# Schematic.net
KiCad netlist of a schematic drawn in Altium Designer
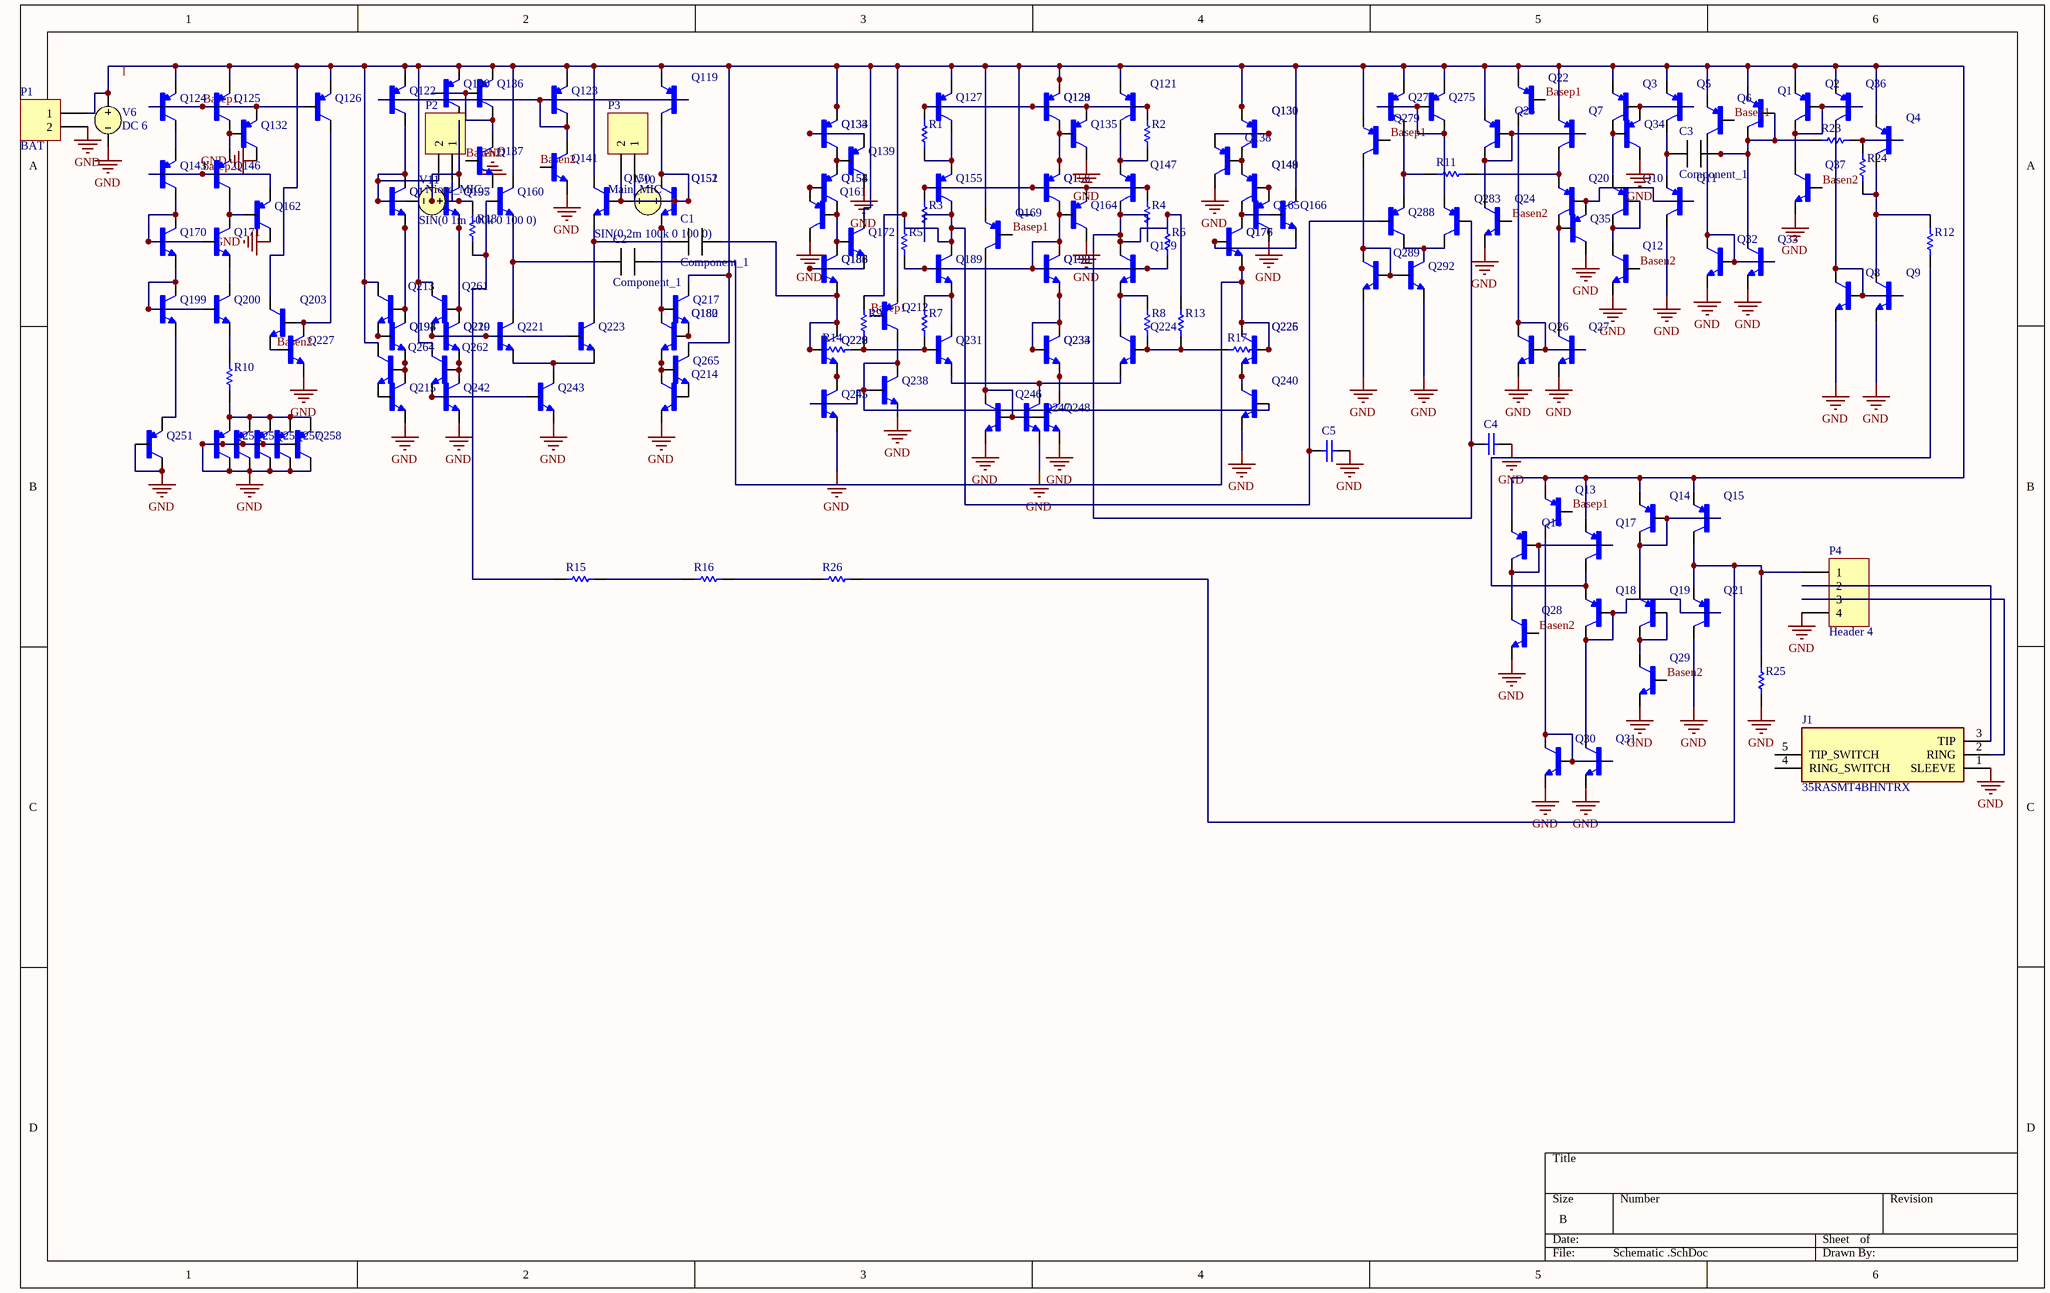
[diagram p0: Schematic .SchDoc]

(export (version "E")
  (design (tool "Eeschema 10.0.6"))
  (components
    (comp (ref "C1")
      (value "Component_1")
      (footprint "Capacitor:PCBComponent_1")
      (libsource (lib "Capacitor") (part "Component_1"))
    )
    (comp (ref "C2")
      (value "Component_1")
      (footprint "Capacitor:PCBComponent_1")
      (libsource (lib "Capacitor") (part "Component_1"))
    )
    (comp (ref "C3")
      (value "Component_1")
      (footprint "Capacitor:PCBComponent_1")
      (libsource (lib "Capacitor") (part "Component_1"))
    )
    (comp (ref "C4")
      (value "Cap")
      (footprint "RAD-0.3")
      (description "Capacitor")
      (fields (field (name "PUBLISHER") "Altium Limited"))
      (libsource (lib "Miscellaneous Devices") (part "Cap"))
    )
    (comp (ref "C5")
      (value "Cap")
      (footprint "RAD-0.3")
      (description "Capacitor")
      (fields (field (name "PUBLISHER") "Altium Limited"))
      (libsource (lib "Miscellaneous Devices") (part "Cap"))
    )
    (comp (ref "J1")
      (value "35RASMT4BHNTRX")
      (footprint "35RASMT4BHNTRX:35RASMT4BHNTRX")
      (description "Phone Connectors SMT 3.5MM PHONE JACK")
      (fields (field (name "MOUSER PART NUMBER") "502-35RASMT4BHNTRX"))
      (libsource (lib "35RASMT4BHNTRX") (part "35RASMT4BHNTRX"))
    )
    (comp (ref "P1")
      (value "BAT")
      (footprint "HDR1X2")
      (description "Header, 2-Pin")
      (fields (field (name "PUBLISHER") "Altium Limited"))
      (libsource (lib "") (part "Header 2_1"))
    )
    (comp (ref "P2")
      (value "Niose_MIC")
      (footprint "HDR1X2")
      (description "Header, 2-Pin")
      (fields (field (name "PUBLISHER") "Altium Limited"))
      (libsource (lib "Miscellaneous Connectors") (part "Header 2"))
    )
    (comp (ref "P3")
      (value "Main_MIC")
      (footprint "HDR1X2")
      (description "Header, 2-Pin")
      (fields (field (name "PUBLISHER") "Altium Limited"))
      (libsource (lib "Miscellaneous Connectors") (part "Header 2"))
    )
    (comp (ref "P4")
      (value "Header 4")
      (footprint "HDR1X4")
      (description "Header, 4-Pin")
      (fields (field (name "PUBLISHER") "Altium Limited"))
      (libsource (lib "Miscellaneous Connectors") (part "Header 4"))
    )
    (comp (ref "Q1")
      (value "KSA992FTA")
      (footprint "KSC1845_KSA992:PCBComponent_1")
      (description "TO-92, 120V, 0.05A,VA=100V,small signal PNP Bipolar Transistor")
      (fields (field (name "MP") "BC337-40 A1G") (field (name "MF") "Taiwan Semiconductor"))
      (libsource (lib "KSA992FTA") (part "KSA992FTA"))
    )
    (comp (ref "Q2")
      (value "KSA992FTA")
      (footprint "KSC1845_KSA992:PCBComponent_1")
      (description "TO-92, 120V, 0.05A,VA=100V,small signal PNP Bipolar Transistor")
      (fields (field (name "MP") "BC337-40 A1G") (field (name "MF") "Taiwan Semiconductor"))
      (libsource (lib "KSA992FTA") (part "KSA992FTA"))
    )
    (comp (ref "Q3")
      (value "KSA992FTA")
      (footprint "KSC1845_KSA992:PCBComponent_1")
      (description "TO-92, 120V, 0.05A,VA=100V,small signal PNP Bipolar Transistor")
      (fields (field (name "MP") "BC337-40 A1G") (field (name "MF") "Taiwan Semiconductor"))
      (libsource (lib "KSA992FTA") (part "KSA992FTA"))
    )
    (comp (ref "Q4")
      (value "KSA992FTA")
      (footprint "KSC1845_KSA992:PCBComponent_1")
      (description "TO-92, 120V, 0.05A,VA=100V,small signal PNP Bipolar Transistor")
      (fields (field (name "MP") "BC337-40 A1G") (field (name "MF") "Taiwan Semiconductor"))
      (libsource (lib "KSA992FTA") (part "KSA992FTA"))
    )
    (comp (ref "Q5")
      (value "KSA992FTA")
      (footprint "KSC1845_KSA992:PCBComponent_1")
      (description "TO-92, 120V, 0.05A,VA=100V,small signal PNP Bipolar Transistor")
      (fields (field (name "MP") "BC337-40 A1G") (field (name "MF") "Taiwan Semiconductor"))
      (libsource (lib "KSA992FTA") (part "KSA992FTA"))
    )
    (comp (ref "Q6")
      (value "BC560B")
      (footprint "BC560_BC550:TO92250P510H770-3")
      (description "TO-92, 45V, 0.1A, PNP Bipolar Transistor")
      (fields (field (name "MP") "BC337-40 A1G") (field (name "MF") "Taiwan Semiconductor"))
      (libsource (lib "") (part "BC560B_1"))
    )
    (comp (ref "Q7")
      (value "KSA992FTA")
      (footprint "KSC1845_KSA992:PCBComponent_1")
      (description "TO-92, 120V, 0.05A,VA=100V,small signal PNP Bipolar Transistor")
      (fields (field (name "MP") "BC337-40 A1G") (field (name "MF") "Taiwan Semiconductor"))
      (libsource (lib "KSA992FTA") (part "KSA992FTA"))
    )
    (comp (ref "Q8")
      (value "KSC1845FTA")
      (footprint "KSC1845_KSA992:PCBComponent_1")
      (description "TO-92, 120V, 0.05A,150VA,small signall NPN Bipolar Transistor")
      (fields (field (name "MP") "BC337-40 A1G") (field (name "MF") "Taiwan Semiconductor"))
      (libsource (lib "") (part "KSC1845FTA_1"))
    )
    (comp (ref "Q9")
      (value "KSC1845FTA")
      (footprint "KSC1845_KSA992:PCBComponent_1")
      (description "TO-92, 120V, 0.05A,150VA,small signall NPN Bipolar Transistor")
      (fields (field (name "MP") "BC337-40 A1G") (field (name "MF") "Taiwan Semiconductor"))
      (libsource (lib "") (part "KSC1845FTA_1"))
    )
    (comp (ref "Q10")
      (value "KSA992FTA")
      (footprint "KSC1845_KSA992:PCBComponent_1")
      (description "TO-92, 120V, 0.05A,VA=100V,small signal PNP Bipolar Transistor")
      (fields (field (name "MP") "BC337-40 A1G") (field (name "MF") "Taiwan Semiconductor"))
      (libsource (lib "KSA992FTA") (part "KSA992FTA"))
    )
    (comp (ref "Q11")
      (value "KSA992FTA")
      (footprint "KSC1845_KSA992:PCBComponent_1")
      (description "TO-92, 120V, 0.05A,VA=100V,small signal PNP Bipolar Transistor")
      (fields (field (name "MP") "BC337-40 A1G") (field (name "MF") "Taiwan Semiconductor"))
      (libsource (lib "KSA992FTA") (part "KSA992FTA"))
    )
    (comp (ref "Q12")
      (value "BC550B")
      (footprint "BC560_BC550:TO92250P510H770-3")
      (description "TO-92, 45V, 0.1A, NPN Bipolar Transistor")
      (fields (field (name "MP") "BC337-40 A1G") (field (name "MF") "Taiwan Semiconductor"))
      (libsource (lib "BC550B") (part "BC550B"))
    )
    (comp (ref "Q13")
      (value "BC560B")
      (footprint "BC560_BC550:TO92250P510H770-3")
      (description "TO-92, 45V, 0.1A, PNP Bipolar Transistor")
      (fields (field (name "MP") "BC337-40 A1G") (field (name "MF") "Taiwan Semiconductor"))
      (libsource (lib "") (part "BC560B_1"))
    )
    (comp (ref "Q14")
      (value "KSA992FTA")
      (footprint "KSC1845_KSA992:PCBComponent_1")
      (description "TO-92, 120V, 0.05A,VA=100V,small signal PNP Bipolar Transistor")
      (fields (field (name "MP") "BC337-40 A1G") (field (name "MF") "Taiwan Semiconductor"))
      (libsource (lib "KSA992FTA") (part "KSA992FTA"))
    )
    (comp (ref "Q15")
      (value "KSA992FTA")
      (footprint "KSC1845_KSA992:PCBComponent_1")
      (description "TO-92, 120V, 0.05A,VA=100V,small signal PNP Bipolar Transistor")
      (fields (field (name "MP") "BC337-40 A1G") (field (name "MF") "Taiwan Semiconductor"))
      (libsource (lib "KSA992FTA") (part "KSA992FTA"))
    )
    (comp (ref "Q16")
      (value "KSA992FTA")
      (footprint "KSC1845_KSA992:PCBComponent_1")
      (description "TO-92, 120V, 0.05A,VA=100V,small signal PNP Bipolar Transistor")
      (fields (field (name "MP") "BC337-40 A1G") (field (name "MF") "Taiwan Semiconductor"))
      (libsource (lib "KSA992FTA") (part "KSA992FTA"))
    )
    (comp (ref "Q17")
      (value "KSA992FTA")
      (footprint "KSC1845_KSA992:PCBComponent_1")
      (description "TO-92, 120V, 0.05A,VA=100V,small signal PNP Bipolar Transistor")
      (fields (field (name "MP") "BC337-40 A1G") (field (name "MF") "Taiwan Semiconductor"))
      (libsource (lib "KSA992FTA") (part "KSA992FTA"))
    )
    (comp (ref "Q18")
      (value "KSA992FTA")
      (footprint "KSC1845_KSA992:PCBComponent_1")
      (description "TO-92, 120V, 0.05A,VA=100V,small signal PNP Bipolar Transistor")
      (fields (field (name "MP") "BC337-40 A1G") (field (name "MF") "Taiwan Semiconductor"))
      (libsource (lib "KSA992FTA") (part "KSA992FTA"))
    )
    (comp (ref "Q19")
      (value "KSA992FTA")
      (footprint "KSC1845_KSA992:PCBComponent_1")
      (description "TO-92, 120V, 0.05A,VA=100V,small signal PNP Bipolar Transistor")
      (fields (field (name "MP") "BC337-40 A1G") (field (name "MF") "Taiwan Semiconductor"))
      (libsource (lib "KSA992FTA") (part "KSA992FTA"))
    )
    (comp (ref "Q20")
      (value "KSA992FTA")
      (footprint "KSC1845_KSA992:PCBComponent_1")
      (description "TO-92, 120V, 0.05A,VA=100V,small signal PNP Bipolar Transistor")
      (fields (field (name "MP") "BC337-40 A1G") (field (name "MF") "Taiwan Semiconductor"))
      (libsource (lib "KSA992FTA") (part "KSA992FTA"))
    )
    (comp (ref "Q21")
      (value "KSA992FTA")
      (footprint "KSC1845_KSA992:PCBComponent_1")
      (description "TO-92, 120V, 0.05A,VA=100V,small signal PNP Bipolar Transistor")
      (fields (field (name "MP") "BC337-40 A1G") (field (name "MF") "Taiwan Semiconductor"))
      (libsource (lib "KSA992FTA") (part "KSA992FTA"))
    )
    (comp (ref "Q22")
      (value "BC560B")
      (footprint "BC560_BC550:TO92250P510H770-3")
      (description "TO-92, 45V, 0.1A, PNP Bipolar Transistor")
      (fields (field (name "MP") "BC337-40 A1G") (field (name "MF") "Taiwan Semiconductor"))
      (libsource (lib "") (part "BC560B_1"))
    )
    (comp (ref "Q23")
      (value "KSA992FTA")
      (footprint "KSC1845_KSA992:PCBComponent_1")
      (description "TO-92, 120V, 0.05A,VA=100V,small signal PNP Bipolar Transistor")
      (fields (field (name "MP") "BC337-40 A1G") (field (name "MF") "Taiwan Semiconductor"))
      (libsource (lib "KSA992FTA") (part "KSA992FTA"))
    )
    (comp (ref "Q24")
      (value "BC550B")
      (footprint "BC560_BC550:TO92250P510H770-3")
      (description "TO-92, 45V, 0.1A, NPN Bipolar Transistor")
      (fields (field (name "MP") "BC337-40 A1G") (field (name "MF") "Taiwan Semiconductor"))
      (libsource (lib "BC550B") (part "BC550B"))
    )
    (comp (ref "Q26")
      (value "KSC1845FTA")
      (footprint "KSC1845_KSA992:PCBComponent_1")
      (description "TO-92, 120V, 0.05A,150VA,small signall NPN Bipolar Transistor")
      (fields (field (name "MP") "BC337-40 A1G") (field (name "MF") "Taiwan Semiconductor"))
      (libsource (lib "") (part "KSC1845FTA_1"))
    )
    (comp (ref "Q27")
      (value "KSC1845FTA")
      (footprint "KSC1845_KSA992:PCBComponent_1")
      (description "TO-92, 120V, 0.05A,150VA,small signall NPN Bipolar Transistor")
      (fields (field (name "MP") "BC337-40 A1G") (field (name "MF") "Taiwan Semiconductor"))
      (libsource (lib "") (part "KSC1845FTA_1"))
    )
    (comp (ref "Q28")
      (value "BC550B")
      (footprint "BC560_BC550:TO92250P510H770-3")
      (description "TO-92, 45V, 0.1A, NPN Bipolar Transistor")
      (fields (field (name "MP") "BC337-40 A1G") (field (name "MF") "Taiwan Semiconductor"))
      (libsource (lib "BC550B") (part "BC550B"))
    )
    (comp (ref "Q29")
      (value "BC550B")
      (footprint "BC560_BC550:TO92250P510H770-3")
      (description "TO-92, 45V, 0.1A, NPN Bipolar Transistor")
      (fields (field (name "MP") "BC337-40 A1G") (field (name "MF") "Taiwan Semiconductor"))
      (libsource (lib "BC550B") (part "BC550B"))
    )
    (comp (ref "Q30")
      (value "KSC1845FTA")
      (footprint "KSC1845_KSA992:PCBComponent_1")
      (description "TO-92, 120V, 0.05A,150VA,small signall NPN Bipolar Transistor")
      (fields (field (name "MP") "BC337-40 A1G") (field (name "MF") "Taiwan Semiconductor"))
      (libsource (lib "") (part "KSC1845FTA_1"))
    )
    (comp (ref "Q31")
      (value "KSC1845FTA")
      (footprint "KSC1845_KSA992:PCBComponent_1")
      (description "TO-92, 120V, 0.05A,150VA,small signall NPN Bipolar Transistor")
      (fields (field (name "MP") "BC337-40 A1G") (field (name "MF") "Taiwan Semiconductor"))
      (libsource (lib "") (part "KSC1845FTA_1"))
    )
    (comp (ref "Q32")
      (value "KSC1845FTA")
      (footprint "KSC1845_KSA992:PCBComponent_1")
      (description "TO-92, 120V, 0.05A,150VA,small signall NPN Bipolar Transistor")
      (fields (field (name "MP") "BC337-40 A1G") (field (name "MF") "Taiwan Semiconductor"))
      (libsource (lib "") (part "KSC1845FTA_1"))
    )
    (comp (ref "Q33")
      (value "KSC1845FTA")
      (footprint "KSC1845_KSA992:PCBComponent_1")
      (description "TO-92, 120V, 0.05A,150VA,small signall NPN Bipolar Transistor")
      (fields (field (name "MP") "BC337-40 A1G") (field (name "MF") "Taiwan Semiconductor"))
      (libsource (lib "") (part "KSC1845FTA_1"))
    )
    (comp (ref "Q34")
      (value "KSA992FTA")
      (footprint "KSC1845_KSA992:PCBComponent_1")
      (description "TO-92, 120V, 0.05A,VA=100V,small signal PNP Bipolar Transistor")
      (fields (field (name "MP") "BC337-40 A1G") (field (name "MF") "Taiwan Semiconductor"))
      (libsource (lib "") (part "KSA992FTA_1"))
    )
    (comp (ref "Q35")
      (value "KSA992FTA")
      (footprint "KSC1845_KSA992:PCBComponent_1")
      (description "TO-92, 120V, 0.05A,VA=100V,small signal PNP Bipolar Transistor")
      (fields (field (name "MP") "BC337-40 A1G") (field (name "MF") "Taiwan Semiconductor"))
      (libsource (lib "") (part "KSA992FTA_1"))
    )
    (comp (ref "Q36")
      (value "KSA992FTA")
      (footprint "KSC1845_KSA992:PCBComponent_1")
      (description "TO-92, 120V, 0.05A,VA=100V,small signal PNP Bipolar Transistor")
      (fields (field (name "MP") "BC337-40 A1G") (field (name "MF") "Taiwan Semiconductor"))
      (libsource (lib "KSA992FTA") (part "KSA992FTA"))
    )
    (comp (ref "Q37")
      (value "BC550B")
      (footprint "BC560_BC550:TO92250P510H770-3")
      (description "TO-92, 45V, 0.1A, NPN Bipolar Transistor")
      (fields (field (name "MP") "BC337-40 A1G") (field (name "MF") "Taiwan Semiconductor"))
      (libsource (lib "BC550B") (part "BC550B"))
    )
    (comp (ref "Q119")
      (value "KSA992FTA")
      (footprint "KSC1845_KSA992:PCBComponent_1")
      (description "TO-92, 120V, 0.05A,VA=100V,small signal PNP Bipolar Transistor")
      (fields (field (name "MP") "BC337-40 A1G") (field (name "MF") "Taiwan Semiconductor"))
      (libsource (lib "KSA992FTA") (part "KSA992FTA"))
    )
    (comp (ref "Q120")
      (value "KSA992FTA")
      (footprint "KSC1845_KSA992:PCBComponent_1")
      (description "TO-92, 120V, 0.05A,VA=100V,small signal PNP Bipolar Transistor")
      (fields (field (name "MP") "BC337-40 A1G") (field (name "MF") "Taiwan Semiconductor"))
      (libsource (lib "") (part "KSA992FTA_1"))
    )
    (comp (ref "Q121")
      (value "KSA992FTA")
      (footprint "KSC1845_KSA992:PCBComponent_1")
      (description "TO-92, 120V, 0.05A,VA=100V,small signal PNP Bipolar Transistor")
      (fields (field (name "MP") "BC337-40 A1G") (field (name "MF") "Taiwan Semiconductor"))
      (libsource (lib "KSA992FTA") (part "KSA992FTA"))
    )
    (comp (ref "Q122")
      (value "KSA992FTA")
      (footprint "KSC1845_KSA992:PCBComponent_1")
      (description "TO-92, 120V, 0.05A,VA=100V,small signal PNP Bipolar Transistor")
      (fields (field (name "MP") "BC337-40 A1G") (field (name "MF") "Taiwan Semiconductor"))
      (libsource (lib "") (part "KSA992FTA_1"))
    )
    (comp (ref "Q123")
      (value "KSA992FTA")
      (footprint "KSC1845_KSA992:PCBComponent_1")
      (description "TO-92, 120V, 0.05A,VA=100V,small signal PNP Bipolar Transistor")
      (fields (field (name "MP") "BC337-40 A1G") (field (name "MF") "Taiwan Semiconductor"))
      (libsource (lib "") (part "KSA992FTA_1"))
    )
    (comp (ref "Q124")
      (value "BC560B")
      (footprint "BC560_BC550:TO92250P510H770-3")
      (description "TO-92, 45V, 0.1A, PNP Bipolar Transistor")
      (fields (field (name "MP") "BC337-40 A1G") (field (name "MF") "Taiwan Semiconductor"))
      (libsource (lib "BC560B") (part "BC560B"))
    )
    (comp (ref "Q125")
      (value "BC560B")
      (footprint "BC560_BC550:TO92250P510H770-3")
      (description "TO-92, 45V, 0.1A, PNP Bipolar Transistor")
      (fields (field (name "MP") "BC337-40 A1G") (field (name "MF") "Taiwan Semiconductor"))
      (libsource (lib "BC560B") (part "BC560B"))
    )
    (comp (ref "Q126")
      (value "BC560B")
      (footprint "BC560_BC550:TO92250P510H770-3")
      (description "TO-92, 45V, 0.1A, PNP Bipolar Transistor")
      (fields (field (name "MP") "BC337-40 A1G") (field (name "MF") "Taiwan Semiconductor"))
      (libsource (lib "BC560B") (part "BC560B"))
    )
    (comp (ref "Q127")
      (value "KSA992FTA")
      (footprint "KSC1845_KSA992:PCBComponent_1")
      (description "TO-92, 120V, 0.05A,VA=100V,small signal PNP Bipolar Transistor")
      (fields (field (name "MP") "BC337-40 A1G") (field (name "MF") "Taiwan Semiconductor"))
      (libsource (lib "") (part "KSA992FTA_1"))
    )
    (comp (ref "Q128")
      (value "KSA992FTA")
      (footprint "KSC1845_KSA992:PCBComponent_1")
      (description "TO-92, 120V, 0.05A,VA=100V,small signal PNP Bipolar Transistor")
      (fields (field (name "MP") "BC337-40 A1G") (field (name "MF") "Taiwan Semiconductor"))
      (libsource (lib "") (part "KSA992FTA_1"))
    )
    (comp (ref "Q129")
      (value "KSA992FTA")
      (footprint "KSC1845_KSA992:PCBComponent_1")
      (description "TO-92, 120V, 0.05A,VA=100V,small signal PNP Bipolar Transistor")
      (fields (field (name "MP") "BC337-40 A1G") (field (name "MF") "Taiwan Semiconductor"))
      (libsource (lib "") (part "KSA992FTA_1"))
    )
    (comp (ref "Q130")
      (value "KSA992FTA")
      (footprint "KSC1845_KSA992:PCBComponent_1")
      (description "TO-92, 120V, 0.05A,VA=100V,small signal PNP Bipolar Transistor")
      (fields (field (name "MP") "BC337-40 A1G") (field (name "MF") "Taiwan Semiconductor"))
      (libsource (lib "KSA992FTA") (part "KSA992FTA"))
    )
    (comp (ref "Q131")
      (value "KSA992FTA")
      (footprint "KSC1845_KSA992:PCBComponent_1")
      (description "TO-92, 120V, 0.05A,VA=100V,small signal PNP Bipolar Transistor")
      (fields (field (name "MP") "BC337-40 A1G") (field (name "MF") "Taiwan Semiconductor"))
      (libsource (lib "KSA992FTA") (part "KSA992FTA"))
    )
    (comp (ref "Q132")
      (value "BC560B")
      (footprint "BC560_BC550:TO92250P510H770-3")
      (description "TO-92, 45V, 0.1A, PNP Bipolar Transistor")
      (fields (field (name "MP") "BC337-40 A1G") (field (name "MF") "Taiwan Semiconductor"))
      (libsource (lib "BC560B") (part "BC560B"))
    )
    (comp (ref "Q133")
      (value "KSA992FTA")
      (footprint "KSC1845_KSA992:PCBComponent_1")
      (description "TO-92, 120V, 0.05A,VA=100V,small signal PNP Bipolar Transistor")
      (fields (field (name "MP") "BC337-40 A1G") (field (name "MF") "Taiwan Semiconductor"))
      (libsource (lib "") (part "KSA992FTA_1"))
    )
    (comp (ref "Q134")
      (value "KSA992FTA")
      (footprint "KSC1845_KSA992:PCBComponent_1")
      (description "TO-92, 120V, 0.05A,VA=100V,small signal PNP Bipolar Transistor")
      (fields (field (name "MP") "BC337-40 A1G") (field (name "MF") "Taiwan Semiconductor"))
      (libsource (lib "") (part "KSA992FTA_1"))
    )
    (comp (ref "Q135")
      (value "KSA992FTA")
      (footprint "KSC1845_KSA992:PCBComponent_1")
      (description "TO-92, 120V, 0.05A,VA=100V,small signal PNP Bipolar Transistor")
      (fields (field (name "MP") "BC337-40 A1G") (field (name "MF") "Taiwan Semiconductor"))
      (libsource (lib "") (part "KSA992FTA_1"))
    )
    (comp (ref "Q136")
      (value "KSA992FTA")
      (footprint "KSC1845_KSA992:PCBComponent_1")
      (description "TO-92, 120V, 0.05A,VA=100V,small signal PNP Bipolar Transistor")
      (fields (field (name "MP") "BC337-40 A1G") (field (name "MF") "Taiwan Semiconductor"))
      (libsource (lib "") (part "KSA992FTA_1"))
    )
    (comp (ref "Q137")
      (value "BC550B")
      (footprint "BC560_BC550:TO92250P510H770-3")
      (description "TO-92, 45V, 0.1A, NPN Bipolar Transistor")
      (fields (field (name "MP") "BC337-40 A1G") (field (name "MF") "Taiwan Semiconductor"))
      (libsource (lib "") (part "BC550B_1"))
    )
    (comp (ref "Q138")
      (value "KSA992FTA")
      (footprint "KSC1845_KSA992:PCBComponent_1")
      (description "TO-92, 120V, 0.05A,VA=100V,small signal PNP Bipolar Transistor")
      (fields (field (name "MP") "BC337-40 A1G") (field (name "MF") "Taiwan Semiconductor"))
      (libsource (lib "KSA992FTA") (part "KSA992FTA"))
    )
    (comp (ref "Q139")
      (value "KSA992FTA")
      (footprint "KSC1845_KSA992:PCBComponent_1")
      (description "TO-92, 120V, 0.05A,VA=100V,small signal PNP Bipolar Transistor")
      (fields (field (name "MP") "BC337-40 A1G") (field (name "MF") "Taiwan Semiconductor"))
      (libsource (lib "") (part "KSA992FTA_1"))
    )
    (comp (ref "Q141")
      (value "BC550B")
      (footprint "BC560_BC550:TO92250P510H770-3")
      (description "TO-92, 45V, 0.1A, NPN Bipolar Transistor")
      (fields (field (name "MP") "BC337-40 A1G") (field (name "MF") "Taiwan Semiconductor"))
      (libsource (lib "") (part "BC550B_1"))
    )
    (comp (ref "Q143")
      (value "BC560B")
      (footprint "BC560_BC550:TO92250P510H770-3")
      (description "TO-92, 45V, 0.1A, PNP Bipolar Transistor")
      (fields (field (name "MP") "BC337-40 A1G") (field (name "MF") "Taiwan Semiconductor"))
      (libsource (lib "BC560B") (part "BC560B"))
    )
    (comp (ref "Q146")
      (value "BC560B")
      (footprint "BC560_BC550:TO92250P510H770-3")
      (description "TO-92, 45V, 0.1A, PNP Bipolar Transistor")
      (fields (field (name "MP") "BC337-40 A1G") (field (name "MF") "Taiwan Semiconductor"))
      (libsource (lib "BC560B") (part "BC560B"))
    )
    (comp (ref "Q147")
      (value "KSA992FTA")
      (footprint "KSC1845_KSA992:PCBComponent_1")
      (description "TO-92, 120V, 0.05A,VA=100V,small signal PNP Bipolar Transistor")
      (fields (field (name "MP") "BC337-40 A1G") (field (name "MF") "Taiwan Semiconductor"))
      (libsource (lib "KSA992FTA") (part "KSA992FTA"))
    )
    (comp (ref "Q148")
      (value "KSA992FTA")
      (footprint "KSC1845_KSA992:PCBComponent_1")
      (description "TO-92, 120V, 0.05A,VA=100V,small signal PNP Bipolar Transistor")
      (fields (field (name "MP") "BC337-40 A1G") (field (name "MF") "Taiwan Semiconductor"))
      (libsource (lib "KSA992FTA") (part "KSA992FTA"))
    )
    (comp (ref "Q149")
      (value "KSA992FTA")
      (footprint "KSC1845_KSA992:PCBComponent_1")
      (description "TO-92, 120V, 0.05A,VA=100V,small signal PNP Bipolar Transistor")
      (fields (field (name "MP") "BC337-40 A1G") (field (name "MF") "Taiwan Semiconductor"))
      (libsource (lib "KSA992FTA") (part "KSA992FTA"))
    )
    (comp (ref "Q150")
      (value "KSC1845FTA")
      (footprint "KSC1845_KSA992:PCBComponent_1")
      (description "TO-92, 120V, 0.05A,150VA,small signall NPN Bipolar Transistor")
      (fields (field (name "MP") "BC337-40 A1G") (field (name "MF") "Taiwan Semiconductor"))
      (libsource (lib "") (part "KSC1845FTA_1"))
    )
    (comp (ref "Q151")
      (value "KSC1845FTA")
      (footprint "KSC1845_KSA992:PCBComponent_1")
      (description "TO-92, 120V, 0.05A,150VA,small signall NPN Bipolar Transistor")
      (fields (field (name "MP") "BC337-40 A1G") (field (name "MF") "Taiwan Semiconductor"))
      (libsource (lib "") (part "KSC1845FTA_1"))
    )
    (comp (ref "Q152")
      (value "KSC1845FTA")
      (footprint "KSC1845_KSA992:PCBComponent_1")
      (description "TO-92, 120V, 0.05A,150VA,small signall NPN Bipolar Transistor")
      (fields (field (name "MP") "BC337-40 A1G") (field (name "MF") "Taiwan Semiconductor"))
      (libsource (lib "") (part "KSC1845FTA_1"))
    )
    (comp (ref "Q153")
      (value "KSA992FTA")
      (footprint "KSC1845_KSA992:PCBComponent_1")
      (description "TO-92, 120V, 0.05A,VA=100V,small signal PNP Bipolar Transistor")
      (fields (field (name "MP") "BC337-40 A1G") (field (name "MF") "Taiwan Semiconductor"))
      (libsource (lib "") (part "KSA992FTA_1"))
    )
    (comp (ref "Q154")
      (value "KSA992FTA")
      (footprint "KSC1845_KSA992:PCBComponent_1")
      (description "TO-92, 120V, 0.05A,VA=100V,small signal PNP Bipolar Transistor")
      (fields (field (name "MP") "BC337-40 A1G") (field (name "MF") "Taiwan Semiconductor"))
      (libsource (lib "") (part "KSA992FTA_1"))
    )
    (comp (ref "Q155")
      (value "KSA992FTA")
      (footprint "KSC1845_KSA992:PCBComponent_1")
      (description "TO-92, 120V, 0.05A,VA=100V,small signal PNP Bipolar Transistor")
      (fields (field (name "MP") "BC337-40 A1G") (field (name "MF") "Taiwan Semiconductor"))
      (libsource (lib "") (part "KSA992FTA_1"))
    )
    (comp (ref "Q156")
      (value "KSA992FTA")
      (footprint "KSC1845_KSA992:PCBComponent_1")
      (description "TO-92, 120V, 0.05A,VA=100V,small signal PNP Bipolar Transistor")
      (fields (field (name "MP") "BC337-40 A1G") (field (name "MF") "Taiwan Semiconductor"))
      (libsource (lib "") (part "KSA992FTA_1"))
    )
    (comp (ref "Q157")
      (value "KSA992FTA")
      (footprint "KSC1845_KSA992:PCBComponent_1")
      (description "TO-92, 120V, 0.05A,VA=100V,small signal PNP Bipolar Transistor")
      (fields (field (name "MP") "BC337-40 A1G") (field (name "MF") "Taiwan Semiconductor"))
      (libsource (lib "") (part "KSA992FTA_1"))
    )
    (comp (ref "Q158")
      (value "KSC1845FTA")
      (footprint "KSC1845_KSA992:PCBComponent_1")
      (description "TO-92, 120V, 0.05A,150VA,small signall NPN Bipolar Transistor")
      (fields (field (name "MP") "BC337-40 A1G") (field (name "MF") "Taiwan Semiconductor"))
      (libsource (lib "KSC1845FTA") (part "KSC1845FTA"))
    )
    (comp (ref "Q159")
      (value "KSC1845FTA")
      (footprint "KSC1845_KSA992:PCBComponent_1")
      (description "TO-92, 120V, 0.05A,150VA,small signall NPN Bipolar Transistor")
      (fields (field (name "MP") "BC337-40 A1G") (field (name "MF") "Taiwan Semiconductor"))
      (libsource (lib "KSC1845FTA") (part "KSC1845FTA"))
    )
    (comp (ref "Q160")
      (value "KSC1845FTA")
      (footprint "KSC1845_KSA992:PCBComponent_1")
      (description "TO-92, 120V, 0.05A,150VA,small signall NPN Bipolar Transistor")
      (fields (field (name "MP") "BC337-40 A1G") (field (name "MF") "Taiwan Semiconductor"))
      (libsource (lib "KSC1845FTA") (part "KSC1845FTA"))
    )
    (comp (ref "Q161")
      (value "KSA992FTA")
      (footprint "KSC1845_KSA992:PCBComponent_1")
      (description "TO-92, 120V, 0.05A,VA=100V,small signal PNP Bipolar Transistor")
      (fields (field (name "MP") "BC337-40 A1G") (field (name "MF") "Taiwan Semiconductor"))
      (libsource (lib "KSA992FTA") (part "KSA992FTA"))
    )
    (comp (ref "Q162")
      (value "BC560B")
      (footprint "BC560_BC550:TO92250P510H770-3")
      (description "TO-92, 45V, 0.1A, PNP Bipolar Transistor")
      (fields (field (name "MP") "BC337-40 A1G") (field (name "MF") "Taiwan Semiconductor"))
      (libsource (lib "BC560B") (part "BC560B"))
    )
    (comp (ref "Q164")
      (value "KSA992FTA")
      (footprint "KSC1845_KSA992:PCBComponent_1")
      (description "TO-92, 120V, 0.05A,VA=100V,small signal PNP Bipolar Transistor")
      (fields (field (name "MP") "BC337-40 A1G") (field (name "MF") "Taiwan Semiconductor"))
      (libsource (lib "") (part "KSA992FTA_1"))
    )
    (comp (ref "Q165")
      (value "KSA992FTA")
      (footprint "KSC1845_KSA992:PCBComponent_1")
      (description "TO-92, 120V, 0.05A,VA=100V,small signal PNP Bipolar Transistor")
      (fields (field (name "MP") "BC337-40 A1G") (field (name "MF") "Taiwan Semiconductor"))
      (libsource (lib "") (part "KSA992FTA_1"))
    )
    (comp (ref "Q166")
      (value "KSC1845FTA")
      (footprint "KSC1845_KSA992:PCBComponent_1")
      (description "TO-92, 120V, 0.05A,150VA,small signall NPN Bipolar Transistor")
      (fields (field (name "MP") "BC337-40 A1G") (field (name "MF") "Taiwan Semiconductor"))
      (libsource (lib "KSC1845FTA") (part "KSC1845FTA"))
    )
    (comp (ref "Q169")
      (value "BC560B")
      (footprint "BC560_BC550:TO92250P510H770-3")
      (description "TO-92, 45V, 0.1A, PNP Bipolar Transistor")
      (fields (field (name "MP") "BC337-40 A1G") (field (name "MF") "Taiwan Semiconductor"))
      (libsource (lib "") (part "BC560B_1"))
    )
    (comp (ref "Q170")
      (value "BC550B")
      (footprint "BC560_BC550:TO92250P510H770-3")
      (description "TO-92, 45V, 0.1A, NPN Bipolar Transistor")
      (fields (field (name "MP") "BC337-40 A1G") (field (name "MF") "Taiwan Semiconductor"))
      (libsource (lib "") (part "BC550B_1"))
    )
    (comp (ref "Q171")
      (value "BC550B")
      (footprint "BC560_BC550:TO92250P510H770-3")
      (description "TO-92, 45V, 0.1A, NPN Bipolar Transistor")
      (fields (field (name "MP") "BC337-40 A1G") (field (name "MF") "Taiwan Semiconductor"))
      (libsource (lib "") (part "BC550B_1"))
    )
    (comp (ref "Q172")
      (value "KSC1845FTA")
      (footprint "KSC1845_KSA992:PCBComponent_1")
      (description "TO-92, 120V, 0.05A,150VA,small signall NPN Bipolar Transistor")
      (fields (field (name "MP") "BC337-40 A1G") (field (name "MF") "Taiwan Semiconductor"))
      (libsource (lib "KSC1845FTA") (part "KSC1845FTA"))
    )
    (comp (ref "Q176")
      (value "KSC1845FTA")
      (footprint "KSC1845_KSA992:PCBComponent_1")
      (description "TO-92, 120V, 0.05A,150VA,small signall NPN Bipolar Transistor")
      (fields (field (name "MP") "BC337-40 A1G") (field (name "MF") "Taiwan Semiconductor"))
      (libsource (lib "KSC1845FTA") (part "KSC1845FTA"))
    )
    (comp (ref "Q177")
      (value "KSC1845FTA")
      (footprint "KSC1845_KSA992:PCBComponent_1")
      (description "TO-92, 120V, 0.05A,150VA,small signall NPN Bipolar Transistor")
      (fields (field (name "MP") "BC337-40 A1G") (field (name "MF") "Taiwan Semiconductor"))
      (libsource (lib "KSC1845FTA") (part "KSC1845FTA"))
    )
    (comp (ref "Q179")
      (value "KSC1845FTA")
      (footprint "KSC1845_KSA992:PCBComponent_1")
      (description "TO-92, 120V, 0.05A,150VA,small signall NPN Bipolar Transistor")
      (fields (field (name "MP") "BC337-40 A1G") (field (name "MF") "Taiwan Semiconductor"))
      (libsource (lib "") (part "KSC1845FTA_1"))
    )
    (comp (ref "Q180")
      (value "KSC1845FTA")
      (footprint "KSC1845_KSA992:PCBComponent_1")
      (description "TO-92, 120V, 0.05A,150VA,small signall NPN Bipolar Transistor")
      (fields (field (name "MP") "BC337-40 A1G") (field (name "MF") "Taiwan Semiconductor"))
      (libsource (lib "") (part "KSC1845FTA_1"))
    )
    (comp (ref "Q182")
      (value "KSC1845FTA")
      (footprint "KSC1845_KSA992:PCBComponent_1")
      (description "TO-92, 120V, 0.05A,150VA,small signall NPN Bipolar Transistor")
      (fields (field (name "MP") "BC337-40 A1G") (field (name "MF") "Taiwan Semiconductor"))
      (libsource (lib "") (part "KSC1845FTA_1"))
    )
    (comp (ref "Q183")
      (value "KSC1845FTA")
      (footprint "KSC1845_KSA992:PCBComponent_1")
      (description "TO-92, 120V, 0.05A,150VA,small signall NPN Bipolar Transistor")
      (fields (field (name "MP") "BC337-40 A1G") (field (name "MF") "Taiwan Semiconductor"))
      (libsource (lib "KSC1845FTA") (part "KSC1845FTA"))
    )
    (comp (ref "Q186")
      (value "KSC1845FTA")
      (footprint "KSC1845_KSA992:PCBComponent_1")
      (description "TO-92, 120V, 0.05A,150VA,small signall NPN Bipolar Transistor")
      (fields (field (name "MP") "BC337-40 A1G") (field (name "MF") "Taiwan Semiconductor"))
      (libsource (lib "KSC1845FTA") (part "KSC1845FTA"))
    )
    (comp (ref "Q189")
      (value "KSC1845FTA")
      (footprint "KSC1845_KSA992:PCBComponent_1")
      (description "TO-92, 120V, 0.05A,150VA,small signall NPN Bipolar Transistor")
      (fields (field (name "MP") "BC337-40 A1G") (field (name "MF") "Taiwan Semiconductor"))
      (libsource (lib "KSC1845FTA") (part "KSC1845FTA"))
    )
    (comp (ref "Q190")
      (value "KSC1845FTA")
      (footprint "KSC1845_KSA992:PCBComponent_1")
      (description "TO-92, 120V, 0.05A,150VA,small signall NPN Bipolar Transistor")
      (fields (field (name "MP") "BC337-40 A1G") (field (name "MF") "Taiwan Semiconductor"))
      (libsource (lib "KSC1845FTA") (part "KSC1845FTA"))
    )
    (comp (ref "Q192")
      (value "KSC1845FTA")
      (footprint "KSC1845_KSA992:PCBComponent_1")
      (description "TO-92, 120V, 0.05A,150VA,small signall NPN Bipolar Transistor")
      (fields (field (name "MP") "BC337-40 A1G") (field (name "MF") "Taiwan Semiconductor"))
      (libsource (lib "KSC1845FTA") (part "KSC1845FTA"))
    )
    (comp (ref "Q193")
      (value "KSC1845FTA")
      (footprint "KSC1845_KSA992:PCBComponent_1")
      (description "TO-92, 120V, 0.05A,150VA,small signall NPN Bipolar Transistor")
      (fields (field (name "MP") "BC337-40 A1G") (field (name "MF") "Taiwan Semiconductor"))
      (libsource (lib "KSC1845FTA") (part "KSC1845FTA"))
    )
    (comp (ref "Q194")
      (value "KSC1845FTA")
      (footprint "KSC1845_KSA992:PCBComponent_1")
      (description "TO-92, 120V, 0.05A,150VA,small signall NPN Bipolar Transistor")
      (fields (field (name "MP") "BC337-40 A1G") (field (name "MF") "Taiwan Semiconductor"))
      (libsource (lib "KSC1845FTA") (part "KSC1845FTA"))
    )
    (comp (ref "Q195")
      (value "KSC1845FTA")
      (footprint "KSC1845_KSA992:PCBComponent_1")
      (description "TO-92, 120V, 0.05A,150VA,small signall NPN Bipolar Transistor")
      (fields (field (name "MP") "BC337-40 A1G") (field (name "MF") "Taiwan Semiconductor"))
      (libsource (lib "KSC1845FTA") (part "KSC1845FTA"))
    )
    (comp (ref "Q197")
      (value "KSC1845FTA")
      (footprint "KSC1845_KSA992:PCBComponent_1")
      (description "TO-92, 120V, 0.05A,150VA,small signall NPN Bipolar Transistor")
      (fields (field (name "MP") "BC337-40 A1G") (field (name "MF") "Taiwan Semiconductor"))
      (libsource (lib "KSC1845FTA") (part "KSC1845FTA"))
    )
    (comp (ref "Q199")
      (value "BC550B")
      (footprint "BC560_BC550:TO92250P510H770-3")
      (description "TO-92, 45V, 0.1A, NPN Bipolar Transistor")
      (fields (field (name "MP") "BC337-40 A1G") (field (name "MF") "Taiwan Semiconductor"))
      (libsource (lib "") (part "BC550B_1"))
    )
    (comp (ref "Q200")
      (value "BC550B")
      (footprint "BC560_BC550:TO92250P510H770-3")
      (description "TO-92, 45V, 0.1A, NPN Bipolar Transistor")
      (fields (field (name "MP") "BC337-40 A1G") (field (name "MF") "Taiwan Semiconductor"))
      (libsource (lib "") (part "BC550B_1"))
    )
    (comp (ref "Q203")
      (value "BC550B")
      (footprint "BC560_BC550:TO92250P510H770-3")
      (description "TO-92, 45V, 0.1A, NPN Bipolar Transistor")
      (fields (field (name "MP") "BC337-40 A1G") (field (name "MF") "Taiwan Semiconductor"))
      (libsource (lib "BC550B") (part "BC550B"))
    )
    (comp (ref "Q212")
      (value "BC560B")
      (footprint "BC560_BC550:TO92250P510H770-3")
      (description "TO-92, 45V, 0.1A, PNP Bipolar Transistor")
      (fields (field (name "MP") "BC337-40 A1G") (field (name "MF") "Taiwan Semiconductor"))
      (libsource (lib "BC560B") (part "BC560B"))
    )
    (comp (ref "Q213")
      (value "KSC1845FTA")
      (footprint "KSC1845_KSA992:PCBComponent_1")
      (description "TO-92, 120V, 0.05A,150VA,small signall NPN Bipolar Transistor")
      (fields (field (name "MP") "BC337-40 A1G") (field (name "MF") "Taiwan Semiconductor"))
      (libsource (lib "") (part "KSC1845FTA_1"))
    )
    (comp (ref "Q214")
      (value "KSC1845FTA")
      (footprint "KSC1845_KSA992:PCBComponent_1")
      (description "TO-92, 120V, 0.05A,150VA,small signall NPN Bipolar Transistor")
      (fields (field (name "MP") "BC337-40 A1G") (field (name "MF") "Taiwan Semiconductor"))
      (libsource (lib "") (part "KSC1845FTA_1"))
    )
    (comp (ref "Q215")
      (value "KSC1845FTA")
      (footprint "KSC1845_KSA992:PCBComponent_1")
      (description "TO-92, 120V, 0.05A,150VA,small signall NPN Bipolar Transistor")
      (fields (field (name "MP") "BC337-40 A1G") (field (name "MF") "Taiwan Semiconductor"))
      (libsource (lib "KSC1845FTA") (part "KSC1845FTA"))
    )
    (comp (ref "Q217")
      (value "KSC1845FTA")
      (footprint "KSC1845_KSA992:PCBComponent_1")
      (description "TO-92, 120V, 0.05A,150VA,small signall NPN Bipolar Transistor")
      (fields (field (name "MP") "BC337-40 A1G") (field (name "MF") "Taiwan Semiconductor"))
      (libsource (lib "KSC1845FTA") (part "KSC1845FTA"))
    )
    (comp (ref "Q219")
      (value "KSC1845FTA")
      (footprint "KSC1845_KSA992:PCBComponent_1")
      (description "TO-92, 120V, 0.05A,150VA,small signall NPN Bipolar Transistor")
      (fields (field (name "MP") "BC337-40 A1G") (field (name "MF") "Taiwan Semiconductor"))
      (libsource (lib "KSC1845FTA") (part "KSC1845FTA"))
    )
    (comp (ref "Q220")
      (value "KSC1845FTA")
      (footprint "KSC1845_KSA992:PCBComponent_1")
      (description "TO-92, 120V, 0.05A,150VA,small signall NPN Bipolar Transistor")
      (fields (field (name "MP") "BC337-40 A1G") (field (name "MF") "Taiwan Semiconductor"))
      (libsource (lib "KSC1845FTA") (part "KSC1845FTA"))
    )
    (comp (ref "Q221")
      (value "KSC1845FTA")
      (footprint "KSC1845_KSA992:PCBComponent_1")
      (description "TO-92, 120V, 0.05A,150VA,small signall NPN Bipolar Transistor")
      (fields (field (name "MP") "BC337-40 A1G") (field (name "MF") "Taiwan Semiconductor"))
      (libsource (lib "KSC1845FTA") (part "KSC1845FTA"))
    )
    (comp (ref "Q223")
      (value "KSC1845FTA")
      (footprint "KSC1845_KSA992:PCBComponent_1")
      (description "TO-92, 120V, 0.05A,150VA,small signall NPN Bipolar Transistor")
      (fields (field (name "MP") "BC337-40 A1G") (field (name "MF") "Taiwan Semiconductor"))
      (libsource (lib "KSC1845FTA") (part "KSC1845FTA"))
    )
    (comp (ref "Q224")
      (value "KSC1845FTA")
      (footprint "KSC1845_KSA992:PCBComponent_1")
      (description "TO-92, 120V, 0.05A,150VA,small signall NPN Bipolar Transistor")
      (fields (field (name "MP") "BC337-40 A1G") (field (name "MF") "Taiwan Semiconductor"))
      (libsource (lib "") (part "KSC1845FTA_1"))
    )
    (comp (ref "Q225")
      (value "KSC1845FTA")
      (footprint "KSC1845_KSA992:PCBComponent_1")
      (description "TO-92, 120V, 0.05A,150VA,small signall NPN Bipolar Transistor")
      (fields (field (name "MP") "BC337-40 A1G") (field (name "MF") "Taiwan Semiconductor"))
      (libsource (lib "") (part "KSC1845FTA_1"))
    )
    (comp (ref "Q226")
      (value "KSC1845FTA")
      (footprint "KSC1845_KSA992:PCBComponent_1")
      (description "TO-92, 120V, 0.05A,150VA,small signall NPN Bipolar Transistor")
      (fields (field (name "MP") "BC337-40 A1G") (field (name "MF") "Taiwan Semiconductor"))
      (libsource (lib "") (part "KSC1845FTA_1"))
    )
    (comp (ref "Q227")
      (value "BC550B")
      (footprint "BC560_BC550:TO92250P510H770-3")
      (description "TO-92, 45V, 0.1A, NPN Bipolar Transistor")
      (fields (field (name "MP") "BC337-40 A1G") (field (name "MF") "Taiwan Semiconductor"))
      (libsource (lib "") (part "BC550B_1"))
    )
    (comp (ref "Q228")
      (value "KSC1845FTA")
      (footprint "KSC1845_KSA992:PCBComponent_1")
      (description "TO-92, 120V, 0.05A,150VA,small signall NPN Bipolar Transistor")
      (fields (field (name "MP") "BC337-40 A1G") (field (name "MF") "Taiwan Semiconductor"))
      (libsource (lib "KSC1845FTA") (part "KSC1845FTA"))
    )
    (comp (ref "Q229")
      (value "KSC1845FTA")
      (footprint "KSC1845_KSA992:PCBComponent_1")
      (description "TO-92, 120V, 0.05A,150VA,small signall NPN Bipolar Transistor")
      (fields (field (name "MP") "BC337-40 A1G") (field (name "MF") "Taiwan Semiconductor"))
      (libsource (lib "KSC1845FTA") (part "KSC1845FTA"))
    )
    (comp (ref "Q231")
      (value "KSC1845FTA")
      (footprint "KSC1845_KSA992:PCBComponent_1")
      (description "TO-92, 120V, 0.05A,150VA,small signall NPN Bipolar Transistor")
      (fields (field (name "MP") "BC337-40 A1G") (field (name "MF") "Taiwan Semiconductor"))
      (libsource (lib "KSC1845FTA") (part "KSC1845FTA"))
    )
    (comp (ref "Q233")
      (value "KSC1845FTA")
      (footprint "KSC1845_KSA992:PCBComponent_1")
      (description "TO-92, 120V, 0.05A,150VA,small signall NPN Bipolar Transistor")
      (fields (field (name "MP") "BC337-40 A1G") (field (name "MF") "Taiwan Semiconductor"))
      (libsource (lib "KSC1845FTA") (part "KSC1845FTA"))
    )
    (comp (ref "Q234")
      (value "KSC1845FTA")
      (footprint "KSC1845_KSA992:PCBComponent_1")
      (description "TO-92, 120V, 0.05A,150VA,small signall NPN Bipolar Transistor")
      (fields (field (name "MP") "BC337-40 A1G") (field (name "MF") "Taiwan Semiconductor"))
      (libsource (lib "KSC1845FTA") (part "KSC1845FTA"))
    )
    (comp (ref "Q238")
      (value "KSC1845FTA")
      (footprint "KSC1845_KSA992:PCBComponent_1")
      (description "TO-92, 120V, 0.05A,150VA,small signall NPN Bipolar Transistor")
      (fields (field (name "MP") "BC337-40 A1G") (field (name "MF") "Taiwan Semiconductor"))
      (libsource (lib "KSC1845FTA") (part "KSC1845FTA"))
    )
    (comp (ref "Q240")
      (value "KSC1845FTA")
      (footprint "KSC1845_KSA992:PCBComponent_1")
      (description "TO-92, 120V, 0.05A,150VA,small signall NPN Bipolar Transistor")
      (fields (field (name "MP") "BC337-40 A1G") (field (name "MF") "Taiwan Semiconductor"))
      (libsource (lib "") (part "KSC1845FTA_1"))
    )
    (comp (ref "Q242")
      (value "KSC1845FTA")
      (footprint "KSC1845_KSA992:PCBComponent_1")
      (description "TO-92, 120V, 0.05A,150VA,small signall NPN Bipolar Transistor")
      (fields (field (name "MP") "BC337-40 A1G") (field (name "MF") "Taiwan Semiconductor"))
      (libsource (lib "KSC1845FTA") (part "KSC1845FTA"))
    )
    (comp (ref "Q243")
      (value "KSC1845FTA")
      (footprint "KSC1845_KSA992:PCBComponent_1")
      (description "TO-92, 120V, 0.05A,150VA,small signall NPN Bipolar Transistor")
      (fields (field (name "MP") "BC337-40 A1G") (field (name "MF") "Taiwan Semiconductor"))
      (libsource (lib "KSC1845FTA") (part "KSC1845FTA"))
    )
    (comp (ref "Q245")
      (value "KSC1845FTA")
      (footprint "KSC1845_KSA992:PCBComponent_1")
      (description "TO-92, 120V, 0.05A,150VA,small signall NPN Bipolar Transistor")
      (fields (field (name "MP") "BC337-40 A1G") (field (name "MF") "Taiwan Semiconductor"))
      (libsource (lib "KSC1845FTA") (part "KSC1845FTA"))
    )
    (comp (ref "Q246")
      (value "KSC1845FTA")
      (footprint "KSC1845_KSA992:PCBComponent_1")
      (description "TO-92, 120V, 0.05A,150VA,small signall NPN Bipolar Transistor")
      (fields (field (name "MP") "BC337-40 A1G") (field (name "MF") "Taiwan Semiconductor"))
      (libsource (lib "") (part "KSC1845FTA_1"))
    )
    (comp (ref "Q247")
      (value "KSC1845FTA")
      (footprint "KSC1845_KSA992:PCBComponent_1")
      (description "TO-92, 120V, 0.05A,150VA,small signall NPN Bipolar Transistor")
      (fields (field (name "MP") "BC337-40 A1G") (field (name "MF") "Taiwan Semiconductor"))
      (libsource (lib "KSC1845FTA") (part "KSC1845FTA"))
    )
    (comp (ref "Q248")
      (value "KSC1845FTA")
      (footprint "KSC1845_KSA992:PCBComponent_1")
      (description "TO-92, 120V, 0.05A,150VA,small signall NPN Bipolar Transistor")
      (fields (field (name "MP") "BC337-40 A1G") (field (name "MF") "Taiwan Semiconductor"))
      (libsource (lib "KSC1845FTA") (part "KSC1845FTA"))
    )
    (comp (ref "Q251")
      (value "BC560B")
      (footprint "BC560_BC550:TO92250P510H770-3")
      (description "TO-92, 45V, 0.1A, PNP Bipolar Transistor")
      (fields (field (name "MP") "BC337-40 A1G") (field (name "MF") "Taiwan Semiconductor"))
      (libsource (lib "BC560B") (part "BC560B"))
    )
    (comp (ref "Q252")
      (value "BC560B")
      (footprint "BC560_BC550:TO92250P510H770-3")
      (description "TO-92, 45V, 0.1A, PNP Bipolar Transistor")
      (fields (field (name "MP") "BC337-40 A1G") (field (name "MF") "Taiwan Semiconductor"))
      (libsource (lib "BC560B") (part "BC560B"))
    )
    (comp (ref "Q254")
      (value "BC560B")
      (footprint "BC560_BC550:TO92250P510H770-3")
      (description "TO-92, 45V, 0.1A, PNP Bipolar Transistor")
      (fields (field (name "MP") "BC337-40 A1G") (field (name "MF") "Taiwan Semiconductor"))
      (libsource (lib "BC560B") (part "BC560B"))
    )
    (comp (ref "Q255")
      (value "BC560B")
      (footprint "BC560_BC550:TO92250P510H770-3")
      (description "TO-92, 45V, 0.1A, PNP Bipolar Transistor")
      (fields (field (name "MP") "BC337-40 A1G") (field (name "MF") "Taiwan Semiconductor"))
      (libsource (lib "BC560B") (part "BC560B"))
    )
    (comp (ref "Q257")
      (value "BC560B")
      (footprint "BC560_BC550:TO92250P510H770-3")
      (description "TO-92, 45V, 0.1A, PNP Bipolar Transistor")
      (fields (field (name "MP") "BC337-40 A1G") (field (name "MF") "Taiwan Semiconductor"))
      (libsource (lib "BC560B") (part "BC560B"))
    )
    (comp (ref "Q258")
      (value "BC560B")
      (footprint "BC560_BC550:TO92250P510H770-3")
      (description "TO-92, 45V, 0.1A, PNP Bipolar Transistor")
      (fields (field (name "MP") "BC337-40 A1G") (field (name "MF") "Taiwan Semiconductor"))
      (libsource (lib "BC560B") (part "BC560B"))
    )
    (comp (ref "Q261")
      (value "KSC1845FTA")
      (footprint "KSC1845_KSA992:PCBComponent_1")
      (description "TO-92, 120V, 0.05A,150VA,small signall NPN Bipolar Transistor")
      (fields (field (name "MP") "BC337-40 A1G") (field (name "MF") "Taiwan Semiconductor"))
      (libsource (lib "") (part "KSC1845FTA_1"))
    )
    (comp (ref "Q262")
      (value "KSC1845FTA")
      (footprint "KSC1845_KSA992:PCBComponent_1")
      (description "TO-92, 120V, 0.05A,150VA,small signall NPN Bipolar Transistor")
      (fields (field (name "MP") "BC337-40 A1G") (field (name "MF") "Taiwan Semiconductor"))
      (libsource (lib "") (part "KSC1845FTA_1"))
    )
    (comp (ref "Q264")
      (value "KSC1845FTA")
      (footprint "KSC1845_KSA992:PCBComponent_1")
      (description "TO-92, 120V, 0.05A,150VA,small signall NPN Bipolar Transistor")
      (fields (field (name "MP") "BC337-40 A1G") (field (name "MF") "Taiwan Semiconductor"))
      (libsource (lib "") (part "KSC1845FTA_1"))
    )
    (comp (ref "Q265")
      (value "KSC1845FTA")
      (footprint "KSC1845_KSA992:PCBComponent_1")
      (description "TO-92, 120V, 0.05A,150VA,small signall NPN Bipolar Transistor")
      (fields (field (name "MP") "BC337-40 A1G") (field (name "MF") "Taiwan Semiconductor"))
      (libsource (lib "KSC1845FTA") (part "KSC1845FTA"))
    )
    (comp (ref "Q274")
      (value "KSA992FTA")
      (footprint "KSC1845_KSA992:PCBComponent_1")
      (description "TO-92, 120V, 0.05A,VA=100V,small signal PNP Bipolar Transistor")
      (fields (field (name "MP") "BC337-40 A1G") (field (name "MF") "Taiwan Semiconductor"))
      (libsource (lib "") (part "KSA992FTA_1"))
    )
    (comp (ref "Q275")
      (value "KSA992FTA")
      (footprint "KSC1845_KSA992:PCBComponent_1")
      (description "TO-92, 120V, 0.05A,VA=100V,small signal PNP Bipolar Transistor")
      (fields (field (name "MP") "BC337-40 A1G") (field (name "MF") "Taiwan Semiconductor"))
      (libsource (lib "") (part "KSA992FTA_1"))
    )
    (comp (ref "Q279")
      (value "BC560B")
      (footprint "BC560_BC550:TO92250P510H770-3")
      (description "TO-92, 45V, 0.1A, PNP Bipolar Transistor")
      (fields (field (name "MP") "BC337-40 A1G") (field (name "MF") "Taiwan Semiconductor"))
      (libsource (lib "") (part "BC560B_1"))
    )
    (comp (ref "Q283")
      (value "KSA992FTA")
      (footprint "KSC1845_KSA992:PCBComponent_1")
      (description "TO-92, 120V, 0.05A,VA=100V,small signal PNP Bipolar Transistor")
      (fields (field (name "MP") "BC337-40 A1G") (field (name "MF") "Taiwan Semiconductor"))
      (libsource (lib "KSA992FTA") (part "KSA992FTA"))
    )
    (comp (ref "Q288")
      (value "KSA992FTA")
      (footprint "KSC1845_KSA992:PCBComponent_1")
      (description "TO-92, 120V, 0.05A,VA=100V,small signal PNP Bipolar Transistor")
      (fields (field (name "MP") "BC337-40 A1G") (field (name "MF") "Taiwan Semiconductor"))
      (libsource (lib "") (part "KSA992FTA_1"))
    )
    (comp (ref "Q289")
      (value "KSC1845FTA")
      (footprint "KSC1845_KSA992:PCBComponent_1")
      (description "TO-92, 120V, 0.05A,150VA,small signall NPN Bipolar Transistor")
      (fields (field (name "MP") "BC337-40 A1G") (field (name "MF") "Taiwan Semiconductor"))
      (libsource (lib "") (part "KSC1845FTA_1"))
    )
    (comp (ref "Q292")
      (value "KSC1845FTA")
      (footprint "KSC1845_KSA992:PCBComponent_1")
      (description "TO-92, 120V, 0.05A,150VA,small signall NPN Bipolar Transistor")
      (fields (field (name "MP") "BC337-40 A1G") (field (name "MF") "Taiwan Semiconductor"))
      (libsource (lib "KSC1845FTA") (part "KSC1845FTA"))
    )
    (comp (ref "R1")
      (value "Res1")
      (footprint "AXIAL-0.3")
      (description "Resistor")
      (fields (field (name "PUBLISHER") "Altium Limited"))
      (libsource (lib "Miscellaneous Devices") (part "Res1"))
    )
    (comp (ref "R2")
      (value "Res1")
      (footprint "AXIAL-0.3")
      (description "Resistor")
      (fields (field (name "PUBLISHER") "Altium Limited"))
      (libsource (lib "Miscellaneous Devices") (part "Res1"))
    )
    (comp (ref "R3")
      (value "Res1")
      (footprint "AXIAL-0.3")
      (description "Resistor")
      (fields (field (name "PUBLISHER") "Altium Limited"))
      (libsource (lib "Miscellaneous Devices") (part "Res1"))
    )
    (comp (ref "R4")
      (value "Res1")
      (footprint "AXIAL-0.3")
      (description "Resistor")
      (fields (field (name "PUBLISHER") "Altium Limited"))
      (libsource (lib "Miscellaneous Devices") (part "Res1"))
    )
    (comp (ref "R5")
      (value "Res1")
      (footprint "AXIAL-0.3")
      (description "Resistor")
      (fields (field (name "PUBLISHER") "Altium Limited"))
      (libsource (lib "Miscellaneous Devices") (part "Res1"))
    )
    (comp (ref "R6")
      (value "Res1")
      (footprint "AXIAL-0.3")
      (description "Resistor")
      (fields (field (name "PUBLISHER") "Altium Limited"))
      (libsource (lib "Miscellaneous Devices") (part "Res1"))
    )
    (comp (ref "R7")
      (value "Res1")
      (footprint "AXIAL-0.3")
      (description "Resistor")
      (fields (field (name "PUBLISHER") "Altium Limited"))
      (libsource (lib "Miscellaneous Devices") (part "Res1"))
    )
    (comp (ref "R8")
      (value "Res1")
      (footprint "AXIAL-0.3")
      (description "Resistor")
      (fields (field (name "PUBLISHER") "Altium Limited"))
      (libsource (lib "Miscellaneous Devices") (part "Res1"))
    )
    (comp (ref "R9")
      (value "Res1")
      (footprint "AXIAL-0.3")
      (description "Resistor")
      (fields (field (name "PUBLISHER") "Altium Limited"))
      (libsource (lib "Miscellaneous Devices") (part "Res1"))
    )
    (comp (ref "R10")
      (value "Res1")
      (footprint "AXIAL-0.3")
      (description "Resistor")
      (fields (field (name "PUBLISHER") "Altium Limited"))
      (libsource (lib "Miscellaneous Devices") (part "Res1"))
    )
    (comp (ref "R11")
      (value "Res1")
      (footprint "AXIAL-0.3")
      (description "Resistor")
      (fields (field (name "PUBLISHER") "Altium Limited"))
      (libsource (lib "Miscellaneous Devices") (part "Res1"))
    )
    (comp (ref "R12")
      (value "Res1")
      (footprint "AXIAL-0.3")
      (description "Resistor")
      (fields (field (name "PUBLISHER") "Altium Limited"))
      (libsource (lib "Miscellaneous Devices") (part "Res1"))
    )
    (comp (ref "R13")
      (value "Res1")
      (footprint "AXIAL-0.3")
      (description "Resistor")
      (fields (field (name "PUBLISHER") "Altium Limited"))
      (libsource (lib "Miscellaneous Devices") (part "Res1"))
    )
    (comp (ref "R14")
      (value "Res1")
      (footprint "AXIAL-0.3")
      (description "Resistor")
      (fields (field (name "PUBLISHER") "Altium Limited"))
      (libsource (lib "Miscellaneous Devices") (part "Res1"))
    )
    (comp (ref "R15")
      (value "Res1")
      (footprint "PCBComponent_1")
      (description "Resistor")
      (fields (field (name "PUBLISHER") "Altium Limited"))
      (libsource (lib "Miscellaneous Devices") (part "Res1"))
    )
    (comp (ref "R16")
      (value "Res1")
      (footprint "PCBComponent_1")
      (description "Resistor")
      (fields (field (name "PUBLISHER") "Altium Limited"))
      (libsource (lib "Miscellaneous Devices") (part "Res1"))
    )
    (comp (ref "R17")
      (value "Res1")
      (footprint "AXIAL-0.3")
      (description "Resistor")
      (fields (field (name "PUBLISHER") "Altium Limited"))
      (libsource (lib "Miscellaneous Devices") (part "Res1"))
    )
    (comp (ref "R18")
      (value "Res1")
      (footprint "AXIAL-0.3")
      (description "Resistor")
      (fields (field (name "PUBLISHER") "Altium Limited"))
      (libsource (lib "Miscellaneous Devices") (part "Res1"))
    )
    (comp (ref "R23")
      (value "Res1")
      (footprint "AXIAL-0.3")
      (description "Resistor")
      (fields (field (name "PUBLISHER") "Altium Limited"))
      (libsource (lib "Miscellaneous Devices") (part "Res1"))
    )
    (comp (ref "R24")
      (value "Res1")
      (footprint "AXIAL-0.3")
      (description "Resistor")
      (fields (field (name "PUBLISHER") "Altium Limited"))
      (libsource (lib "Miscellaneous Devices") (part "Res1"))
    )
    (comp (ref "R25")
      (value "Res1")
      (footprint "AXIAL-0.3")
      (description "Resistor")
      (fields (field (name "PUBLISHER") "Altium Limited"))
      (libsource (lib "Miscellaneous Devices") (part "Res1"))
    )
    (comp (ref "R26")
      (value "Res1")
      (footprint "AXIAL-0.3")
      (description "Resistor")
      (fields (field (name "PUBLISHER") "Altium Limited"))
      (libsource (lib "Miscellaneous Devices") (part "Res1"))
    )
    (comp (ref "V6")
      (value "DC 6")
      (description "Voltage Source")
      (fields (field (name "PUBLISHER") "Altium Limited"))
      (libsource (lib "Simulation Generic Components") (part "VSRC"))
    )
    (comp (ref "V10")
      (value "SIN(0 2m 100k 0 100 0)")
      (description "Voltage Source")
      (fields (field (name "PUBLISHER") "Altium Limited"))
      (libsource (lib "Simulation Generic Components") (part "VSRC"))
    )
    (comp (ref "V11")
      (value "SIN(0 1m 100k 0 100 0)")
      (description "Voltage Source")
      (fields (field (name "PUBLISHER") "Altium Limited"))
      (libsource (lib "Simulation Generic Components") (part "VSRC"))
    )
  )
  (nets
    (net (code "1") (name "/Basen2") (class "Default")
      (node (ref "Q12") (pin "2") (pinfunction "B_2") (pintype "passive"))
      (node (ref "Q137") (pin "2") (pinfunction "B_2") (pintype "passive"))
      (node (ref "Q141") (pin "2") (pinfunction "B_2") (pintype "passive"))
      (node (ref "Q203") (pin "3") (pinfunction "E_3") (pintype "passive"))
      (node (ref "Q227") (pin "2") (pinfunction "B_2") (pintype "passive"))
      (node (ref "Q24") (pin "2") (pinfunction "B_2") (pintype "passive"))
      (node (ref "Q28") (pin "2") (pinfunction "B_2") (pintype "passive"))
      (node (ref "Q29") (pin "2") (pinfunction "B_2") (pintype "passive"))
      (node (ref "Q37") (pin "2") (pinfunction "B_2") (pintype "passive"))
    )
    (net (code "2") (name "/Basep1") (class "Default")
      (node (ref "Q124") (pin "2") (pinfunction "B_2") (pintype "passive"))
      (node (ref "Q125") (pin "2") (pinfunction "B_2") (pintype "passive"))
      (node (ref "Q126") (pin "2") (pinfunction "B_2") (pintype "passive"))
      (node (ref "Q13") (pin "2") (pinfunction "B_2") (pintype "passive"))
      (node (ref "Q132") (pin "3") (pinfunction "E_3") (pintype "passive"))
      (node (ref "Q169") (pin "2") (pinfunction "B_2") (pintype "passive"))
      (node (ref "Q212") (pin "2") (pinfunction "B_2") (pintype "passive"))
      (node (ref "Q22") (pin "2") (pinfunction "B_2") (pintype "passive"))
      (node (ref "Q279") (pin "2") (pinfunction "B_2") (pintype "passive"))
      (node (ref "Q6") (pin "2") (pinfunction "B_2") (pintype "passive"))
    )
    (net (code "3") (name "/basep2") (class "Default")
      (node (ref "Q143") (pin "2") (pinfunction "B_2") (pintype "passive"))
      (node (ref "Q146") (pin "2") (pinfunction "B_2") (pintype "passive"))
      (node (ref "Q162") (pin "3") (pinfunction "E_3") (pintype "passive"))
    )
    (net (code "4") (name "GND") (class "Default")
      (node (ref "C4") (pin "2") (pinfunction "2_2") (pintype "passive"))
      (node (ref "C5") (pin "2") (pinfunction "2_2") (pintype "passive"))
      (node (ref "J1") (pin "1") (pinfunction "SLEEVE_1") (pintype "passive"))
      (node (ref "P1") (pin "2") (pinfunction "2_2") (pintype "passive"))
      (node (ref "P4") (pin "4") (pinfunction "4_4") (pintype "passive"))
      (node (ref "Q11") (pin "2") (pinfunction "C_2") (pintype "passive"))
      (node (ref "Q12") (pin "3") (pinfunction "E_3") (pintype "passive"))
      (node (ref "Q132") (pin "1") (pinfunction "C_1") (pintype "passive"))
      (node (ref "Q135") (pin "2") (pinfunction "C_2") (pintype "passive"))
      (node (ref "Q137") (pin "3") (pinfunction "E_3") (pintype "passive"))
      (node (ref "Q138") (pin "2") (pinfunction "C_2") (pintype "passive"))
      (node (ref "Q139") (pin "2") (pinfunction "C_2") (pintype "passive"))
      (node (ref "Q141") (pin "3") (pinfunction "E_3") (pintype "passive"))
      (node (ref "Q161") (pin "2") (pinfunction "C_2") (pintype "passive"))
      (node (ref "Q162") (pin "1") (pinfunction "C_1") (pintype "passive"))
      (node (ref "Q164") (pin "2") (pinfunction "C_2") (pintype "passive"))
      (node (ref "Q165") (pin "2") (pinfunction "C_2") (pintype "passive"))
      (node (ref "Q21") (pin "2") (pinfunction "C_2") (pintype "passive"))
      (node (ref "Q214") (pin "1") (pinfunction "E_1") (pintype "passive"))
      (node (ref "Q215") (pin "1") (pinfunction "E_1") (pintype "passive"))
      (node (ref "Q227") (pin "3") (pinfunction "E_3") (pintype "passive"))
      (node (ref "Q238") (pin "1") (pinfunction "E_1") (pintype "passive"))
      (node (ref "Q24") (pin "3") (pinfunction "E_3") (pintype "passive"))
      (node (ref "Q240") (pin "1") (pinfunction "E_1") (pintype "passive"))
      (node (ref "Q242") (pin "1") (pinfunction "E_1") (pintype "passive"))
      (node (ref "Q243") (pin "1") (pinfunction "E_1") (pintype "passive"))
      (node (ref "Q245") (pin "1") (pinfunction "E_1") (pintype "passive"))
      (node (ref "Q246") (pin "1") (pinfunction "E_1") (pintype "passive"))
      (node (ref "Q247") (pin "1") (pinfunction "E_1") (pintype "passive"))
      (node (ref "Q248") (pin "1") (pinfunction "E_1") (pintype "passive"))
      (node (ref "Q251") (pin "1") (pinfunction "C_1") (pintype "passive"))
      (node (ref "Q251") (pin "2") (pinfunction "B_2") (pintype "passive"))
      (node (ref "Q252") (pin "1") (pinfunction "C_1") (pintype "passive"))
      (node (ref "Q252") (pin "2") (pinfunction "B_2") (pintype "passive"))
      (node (ref "Q254") (pin "1") (pinfunction "C_1") (pintype "passive"))
      (node (ref "Q254") (pin "2") (pinfunction "B_2") (pintype "passive"))
      (node (ref "Q255") (pin "1") (pinfunction "C_1") (pintype "passive"))
      (node (ref "Q255") (pin "2") (pinfunction "B_2") (pintype "passive"))
      (node (ref "Q257") (pin "1") (pinfunction "C_1") (pintype "passive"))
      (node (ref "Q257") (pin "2") (pinfunction "B_2") (pintype "passive"))
      (node (ref "Q258") (pin "1") (pinfunction "C_1") (pintype "passive"))
      (node (ref "Q258") (pin "2") (pinfunction "B_2") (pintype "passive"))
      (node (ref "Q26") (pin "1") (pinfunction "E_1") (pintype "passive"))
      (node (ref "Q27") (pin "1") (pinfunction "E_1") (pintype "passive"))
      (node (ref "Q28") (pin "3") (pinfunction "E_3") (pintype "passive"))
      (node (ref "Q289") (pin "1") (pinfunction "E_1") (pintype "passive"))
      (node (ref "Q29") (pin "3") (pinfunction "E_3") (pintype "passive"))
      (node (ref "Q292") (pin "1") (pinfunction "E_1") (pintype "passive"))
      (node (ref "Q30") (pin "1") (pinfunction "E_1") (pintype "passive"))
      (node (ref "Q31") (pin "1") (pinfunction "E_1") (pintype "passive"))
      (node (ref "Q32") (pin "1") (pinfunction "E_1") (pintype "passive"))
      (node (ref "Q33") (pin "1") (pinfunction "E_1") (pintype "passive"))
      (node (ref "Q34") (pin "2") (pinfunction "C_2") (pintype "passive"))
      (node (ref "Q35") (pin "2") (pinfunction "C_2") (pintype "passive"))
      (node (ref "Q37") (pin "3") (pinfunction "E_3") (pintype "passive"))
      (node (ref "Q8") (pin "1") (pinfunction "E_1") (pintype "passive"))
      (node (ref "Q9") (pin "1") (pinfunction "E_1") (pintype "passive"))
      (node (ref "R25") (pin "2") (pinfunction "2_2") (pintype "passive"))
      (node (ref "V6") (pin "2") (pinfunction "2_2") (pintype "passive"))
    )
    (net (code "5") (name "Net-(J1-RING)") (class "Default")
      (node (ref "J1") (pin "2") (pinfunction "RING_2") (pintype "passive"))
      (node (ref "P4") (pin "3") (pinfunction "3_3") (pintype "passive"))
    )
    (net (code "6") (name "Net-(J1-TIP)") (class "Default")
      (node (ref "J1") (pin "3") (pinfunction "TIP_3") (pintype "passive"))
      (node (ref "P4") (pin "2") (pinfunction "2_2") (pintype "passive"))
    )
    (net (code "7") (name "Net-(P2-Pad1)") (class "Default")
      (node (ref "P2") (pin "1") (pinfunction "1_1") (pintype "passive"))
      (node (ref "R18") (pin "1") (pinfunction "1_1") (pintype "passive"))
      (node (ref "V11") (pin "1") (pinfunction "1_1") (pintype "passive"))
    )
    (net (code "8") (name "Net-(Q1-B)") (class "Default")
      (node (ref "C3") (pin "2") (pinfunction "2_2") (pintype "passive"))
      (node (ref "Q1") (pin "2") (pinfunction "C_2") (pintype "passive"))
      (node (ref "Q1") (pin "3") (pinfunction "B_3") (pintype "passive"))
      (node (ref "Q33") (pin "2") (pinfunction "C_2") (pintype "passive"))
      (node (ref "R23") (pin "1") (pinfunction "1_1") (pintype "passive"))
    )
    (net (code "9") (name "Net-(Q1-E)") (class "Default")
      (node (ref "P1") (pin "1") (pinfunction "1_1") (pintype "passive"))
      (node (ref "Q1") (pin "1") (pinfunction "E_1") (pintype "passive"))
      (node (ref "Q119") (pin "1") (pinfunction "E_1") (pintype "passive"))
      (node (ref "Q120") (pin "1") (pinfunction "E_1") (pintype "passive"))
      (node (ref "Q121") (pin "1") (pinfunction "E_1") (pintype "passive"))
      (node (ref "Q122") (pin "1") (pinfunction "E_1") (pintype "passive"))
      (node (ref "Q123") (pin "1") (pinfunction "E_1") (pintype "passive"))
      (node (ref "Q124") (pin "3") (pinfunction "E_3") (pintype "passive"))
      (node (ref "Q125") (pin "3") (pinfunction "E_3") (pintype "passive"))
      (node (ref "Q126") (pin "3") (pinfunction "E_3") (pintype "passive"))
      (node (ref "Q127") (pin "1") (pinfunction "E_1") (pintype "passive"))
      (node (ref "Q128") (pin "1") (pinfunction "E_1") (pintype "passive"))
      (node (ref "Q129") (pin "1") (pinfunction "E_1") (pintype "passive"))
      (node (ref "Q13") (pin "3") (pinfunction "E_3") (pintype "passive"))
      (node (ref "Q130") (pin "1") (pinfunction "E_1") (pintype "passive"))
      (node (ref "Q131") (pin "1") (pinfunction "E_1") (pintype "passive"))
      (node (ref "Q133") (pin "1") (pinfunction "E_1") (pintype "passive"))
      (node (ref "Q134") (pin "1") (pinfunction "E_1") (pintype "passive"))
      (node (ref "Q136") (pin "1") (pinfunction "E_1") (pintype "passive"))
      (node (ref "Q14") (pin "1") (pinfunction "E_1") (pintype "passive"))
      (node (ref "Q15") (pin "1") (pinfunction "E_1") (pintype "passive"))
      (node (ref "Q150") (pin "2") (pinfunction "C_2") (pintype "passive"))
      (node (ref "Q16") (pin "1") (pinfunction "E_1") (pintype "passive"))
      (node (ref "Q160") (pin "2") (pinfunction "C_2") (pintype "passive"))
      (node (ref "Q166") (pin "2") (pinfunction "C_2") (pintype "passive"))
      (node (ref "Q169") (pin "3") (pinfunction "E_3") (pintype "passive"))
      (node (ref "Q17") (pin "1") (pinfunction "E_1") (pintype "passive"))
      (node (ref "Q172") (pin "2") (pinfunction "C_2") (pintype "passive"))
      (node (ref "Q2") (pin "1") (pinfunction "E_1") (pintype "passive"))
      (node (ref "Q203") (pin "1") (pinfunction "C_1") (pintype "passive"))
      (node (ref "Q212") (pin "3") (pinfunction "E_3") (pintype "passive"))
      (node (ref "Q213") (pin "2") (pinfunction "C_2") (pintype "passive"))
      (node (ref "Q217") (pin "2") (pinfunction "C_2") (pintype "passive"))
      (node (ref "Q22") (pin "3") (pinfunction "E_3") (pintype "passive"))
      (node (ref "Q23") (pin "1") (pinfunction "E_1") (pintype "passive"))
      (node (ref "Q261") (pin "2") (pinfunction "C_2") (pintype "passive"))
      (node (ref "Q262") (pin "2") (pinfunction "C_2") (pintype "passive"))
      (node (ref "Q264") (pin "2") (pinfunction "C_2") (pintype "passive"))
      (node (ref "Q265") (pin "2") (pinfunction "C_2") (pintype "passive"))
      (node (ref "Q274") (pin "1") (pinfunction "E_1") (pintype "passive"))
      (node (ref "Q275") (pin "1") (pinfunction "E_1") (pintype "passive"))
      (node (ref "Q279") (pin "3") (pinfunction "E_3") (pintype "passive"))
      (node (ref "Q3") (pin "1") (pinfunction "E_1") (pintype "passive"))
      (node (ref "Q36") (pin "1") (pinfunction "E_1") (pintype "passive"))
      (node (ref "Q4") (pin "1") (pinfunction "E_1") (pintype "passive"))
      (node (ref "Q5") (pin "1") (pinfunction "E_1") (pintype "passive"))
      (node (ref "Q6") (pin "3") (pinfunction "E_3") (pintype "passive"))
      (node (ref "Q7") (pin "1") (pinfunction "E_1") (pintype "passive"))
      (node (ref "V6") (pin "1") (pinfunction "1_1") (pintype "passive"))
    )
    (net (code "10") (name "Net-(Q2-B)") (class "Default")
      (node (ref "Q2") (pin "2") (pinfunction "C_2") (pintype "passive"))
      (node (ref "Q2") (pin "3") (pinfunction "B_3") (pintype "passive"))
      (node (ref "Q36") (pin "3") (pinfunction "B_3") (pintype "passive"))
      (node (ref "Q37") (pin "1") (pinfunction "C_1") (pintype "passive"))
    )
    (net (code "11") (name "Net-(Q3-B)") (class "Default")
      (node (ref "Q3") (pin "3") (pinfunction "B_3") (pintype "passive"))
      (node (ref "Q34") (pin "1") (pinfunction "E_1") (pintype "passive"))
      (node (ref "Q5") (pin "3") (pinfunction "B_3") (pintype "passive"))
    )
    (net (code "12") (name "Net-(Q4-B)") (class "Default")
      (node (ref "Q4") (pin "3") (pinfunction "B_3") (pintype "passive"))
      (node (ref "R23") (pin "2") (pinfunction "2_2") (pintype "passive"))
      (node (ref "R24") (pin "2") (pinfunction "2_2") (pintype "passive"))
    )
    (net (code "13") (name "Net-(Q4-C)") (class "Default")
      (node (ref "Q4") (pin "2") (pinfunction "C_2") (pintype "passive"))
      (node (ref "Q9") (pin "2") (pinfunction "C_2") (pintype "passive"))
      (node (ref "R12") (pin "1") (pinfunction "1_1") (pintype "passive"))
      (node (ref "R24") (pin "1") (pinfunction "1_1") (pintype "passive"))
    )
    (net (code "14") (name "Net-(Q10-B)") (class "Default")
      (node (ref "Q10") (pin "2") (pinfunction "C_2") (pintype "passive"))
      (node (ref "Q10") (pin "3") (pinfunction "B_3") (pintype "passive"))
      (node (ref "Q12") (pin "1") (pinfunction "C_1") (pintype "passive"))
    )
    (net (code "15") (name "Net-(Q10-E)") (class "Default")
      (node (ref "Q10") (pin "1") (pinfunction "E_1") (pintype "passive"))
      (node (ref "Q3") (pin "2") (pinfunction "C_2") (pintype "passive"))
      (node (ref "Q34") (pin "3") (pinfunction "B_3") (pintype "passive"))
    )
    (net (code "16") (name "Net-(Q11-B)") (class "Default")
      (node (ref "Q11") (pin "3") (pinfunction "B_3") (pintype "passive"))
      (node (ref "Q20") (pin "3") (pinfunction "B_3") (pintype "passive"))
      (node (ref "Q35") (pin "1") (pinfunction "E_1") (pintype "passive"))
    )
    (net (code "17") (name "Net-(Q11-E)") (class "Default")
      (node (ref "C3") (pin "1") (pinfunction "1_1") (pintype "passive"))
      (node (ref "Q11") (pin "1") (pinfunction "E_1") (pintype "passive"))
      (node (ref "Q5") (pin "2") (pinfunction "C_2") (pintype "passive"))
    )
    (net (code "18") (name "Net-(Q13-C)") (class "Default")
      (node (ref "Q13") (pin "1") (pinfunction "C_1") (pintype "passive"))
      (node (ref "Q30") (pin "2") (pinfunction "C_2") (pintype "passive"))
      (node (ref "Q30") (pin "3") (pinfunction "B_3") (pintype "passive"))
      (node (ref "Q31") (pin "3") (pinfunction "B_3") (pintype "passive"))
    )
    (net (code "19") (name "Net-(Q14-B)") (class "Default")
      (node (ref "Q14") (pin "2") (pinfunction "C_2") (pintype "passive"))
      (node (ref "Q14") (pin "3") (pinfunction "B_3") (pintype "passive"))
      (node (ref "Q15") (pin "3") (pinfunction "B_3") (pintype "passive"))
      (node (ref "Q19") (pin "1") (pinfunction "E_1") (pintype "passive"))
    )
    (net (code "20") (name "Net-(Q15-C)") (class "Default")
      (node (ref "P4") (pin "1") (pinfunction "1_1") (pintype "passive"))
      (node (ref "Q15") (pin "2") (pinfunction "C_2") (pintype "passive"))
      (node (ref "Q21") (pin "1") (pinfunction "E_1") (pintype "passive"))
      (node (ref "R25") (pin "1") (pinfunction "1_1") (pintype "passive"))
      (node (ref "R26") (pin "2") (pinfunction "2_2") (pintype "passive"))
    )
    (net (code "21") (name "Net-(Q16-B)") (class "Default")
      (node (ref "Q16") (pin "2") (pinfunction "C_2") (pintype "passive"))
      (node (ref "Q16") (pin "3") (pinfunction "B_3") (pintype "passive"))
      (node (ref "Q17") (pin "3") (pinfunction "B_3") (pintype "passive"))
      (node (ref "Q28") (pin "1") (pinfunction "C_1") (pintype "passive"))
    )
    (net (code "22") (name "Net-(Q17-C)") (class "Default")
      (node (ref "Q17") (pin "2") (pinfunction "C_2") (pintype "passive"))
      (node (ref "Q18") (pin "1") (pinfunction "E_1") (pintype "passive"))
      (node (ref "R12") (pin "2") (pinfunction "2_2") (pintype "passive"))
    )
    (net (code "23") (name "Net-(Q18-B)") (class "Default")
      (node (ref "Q18") (pin "2") (pinfunction "C_2") (pintype "passive"))
      (node (ref "Q18") (pin "3") (pinfunction "B_3") (pintype "passive"))
      (node (ref "Q21") (pin "3") (pinfunction "B_3") (pintype "passive"))
      (node (ref "Q31") (pin "2") (pinfunction "C_2") (pintype "passive"))
    )
    (net (code "24") (name "Net-(Q19-B)") (class "Default")
      (node (ref "Q19") (pin "2") (pinfunction "C_2") (pintype "passive"))
      (node (ref "Q19") (pin "3") (pinfunction "B_3") (pintype "passive"))
      (node (ref "Q29") (pin "1") (pinfunction "C_1") (pintype "passive"))
    )
    (net (code "25") (name "Net-(Q20-C)") (class "Default")
      (node (ref "Q20") (pin "2") (pinfunction "C_2") (pintype "passive"))
      (node (ref "Q27") (pin "2") (pinfunction "C_2") (pintype "passive"))
      (node (ref "Q35") (pin "3") (pinfunction "B_3") (pintype "passive"))
    )
    (net (code "26") (name "Net-(Q20-E)") (class "Default")
      (node (ref "Q20") (pin "1") (pinfunction "E_1") (pintype "passive"))
      (node (ref "Q7") (pin "2") (pinfunction "C_2") (pintype "passive"))
      (node (ref "R11") (pin "2") (pinfunction "2_2") (pintype "passive"))
    )
    (net (code "27") (name "Net-(Q22-C)") (class "Default")
      (node (ref "Q22") (pin "1") (pinfunction "C_1") (pintype "passive"))
      (node (ref "Q26") (pin "2") (pinfunction "C_2") (pintype "passive"))
      (node (ref "Q26") (pin "3") (pinfunction "B_3") (pintype "passive"))
      (node (ref "Q27") (pin "3") (pinfunction "B_3") (pintype "passive"))
    )
    (net (code "28") (name "Net-(Q23-B)") (class "Default")
      (node (ref "Q23") (pin "2") (pinfunction "C_2") (pintype "passive"))
      (node (ref "Q23") (pin "3") (pinfunction "B_3") (pintype "passive"))
      (node (ref "Q24") (pin "1") (pinfunction "C_1") (pintype "passive"))
      (node (ref "Q7") (pin "3") (pinfunction "B_3") (pintype "passive"))
    )
    (net (code "29") (name "Net-(Q32-B)") (class "Default")
      (node (ref "Q32") (pin "2") (pinfunction "C_2") (pintype "passive"))
      (node (ref "Q32") (pin "3") (pinfunction "B_3") (pintype "passive"))
      (node (ref "Q33") (pin "3") (pinfunction "B_3") (pintype "passive"))
      (node (ref "Q6") (pin "1") (pinfunction "C_1") (pintype "passive"))
    )
    (net (code "30") (name "Net-(Q36-C)") (class "Default")
      (node (ref "Q36") (pin "2") (pinfunction "C_2") (pintype "passive"))
      (node (ref "Q8") (pin "2") (pinfunction "C_2") (pintype "passive"))
      (node (ref "Q8") (pin "3") (pinfunction "B_3") (pintype "passive"))
      (node (ref "Q9") (pin "3") (pinfunction "B_3") (pintype "passive"))
    )
    (net (code "31") (name "Net-(Q119-B)") (class "Default")
      (node (ref "Q119") (pin "3") (pinfunction "B_3") (pintype "passive"))
      (node (ref "Q122") (pin "3") (pinfunction "B_3") (pintype "passive"))
      (node (ref "Q123") (pin "2") (pinfunction "C_2") (pintype "passive"))
      (node (ref "Q123") (pin "3") (pinfunction "B_3") (pintype "passive"))
      (node (ref "Q141") (pin "1") (pinfunction "C_1") (pintype "passive"))
    )
    (net (code "32") (name "Net-(Q119-C)") (class "Default")
      (node (ref "P3") (pin "1") (pinfunction "1_1") (pintype "passive"))
      (node (ref "Q119") (pin "2") (pinfunction "C_2") (pintype "passive"))
      (node (ref "Q151") (pin "2") (pinfunction "C_2") (pintype "passive"))
      (node (ref "Q151") (pin "3") (pinfunction "B_3") (pintype "passive"))
      (node (ref "Q152") (pin "2") (pinfunction "C_2") (pintype "passive"))
      (node (ref "Q152") (pin "3") (pinfunction "B_3") (pintype "passive"))
      (node (ref "V10") (pin "2") (pinfunction "2_2") (pintype "passive"))
    )
    (net (code "33") (name "Net-(Q120-B)") (class "Default")
      (node (ref "Q120") (pin "3") (pinfunction "B_3") (pintype "passive"))
      (node (ref "Q136") (pin "2") (pinfunction "C_2") (pintype "passive"))
      (node (ref "Q136") (pin "3") (pinfunction "B_3") (pintype "passive"))
      (node (ref "Q137") (pin "1") (pinfunction "C_1") (pintype "passive"))
    )
    (net (code "34") (name "Net-(Q120-C)") (class "Default")
      (node (ref "Q120") (pin "2") (pinfunction "C_2") (pintype "passive"))
      (node (ref "Q195") (pin "2") (pinfunction "C_2") (pintype "passive"))
      (node (ref "Q195") (pin "3") (pinfunction "B_3") (pintype "passive"))
      (node (ref "Q197") (pin "2") (pinfunction "C_2") (pintype "passive"))
      (node (ref "Q197") (pin "3") (pinfunction "B_3") (pintype "passive"))
    )
    (net (code "35") (name "Net-(Q121-B)") (class "Default")
      (node (ref "Q121") (pin "3") (pinfunction "B_3") (pintype "passive"))
      (node (ref "Q127") (pin "3") (pinfunction "B_3") (pintype "passive"))
      (node (ref "Q128") (pin "3") (pinfunction "B_3") (pintype "passive"))
      (node (ref "Q129") (pin "3") (pinfunction "B_3") (pintype "passive"))
      (node (ref "Q135") (pin "1") (pinfunction "E_1") (pintype "passive"))
      (node (ref "R1") (pin "2") (pinfunction "2_2") (pintype "passive"))
      (node (ref "R2") (pin "2") (pinfunction "2_2") (pintype "passive"))
    )
    (net (code "36") (name "Net-(Q121-C)") (class "Default")
      (node (ref "Q121") (pin "2") (pinfunction "C_2") (pintype "passive"))
      (node (ref "Q147") (pin "1") (pinfunction "E_1") (pintype "passive"))
      (node (ref "R2") (pin "1") (pinfunction "1_1") (pintype "passive"))
    )
    (net (code "37") (name "Net-(Q122-C)") (class "Default")
      (node (ref "P2") (pin "2") (pinfunction "2_2") (pintype "passive"))
      (node (ref "Q122") (pin "2") (pinfunction "C_2") (pintype "passive"))
      (node (ref "Q158") (pin "2") (pinfunction "C_2") (pintype "passive"))
      (node (ref "Q158") (pin "3") (pinfunction "B_3") (pintype "passive"))
      (node (ref "Q159") (pin "2") (pinfunction "C_2") (pintype "passive"))
      (node (ref "Q159") (pin "3") (pinfunction "B_3") (pintype "passive"))
      (node (ref "V11") (pin "2") (pinfunction "2_2") (pintype "passive"))
    )
    (net (code "38") (name "Net-(Q124-C)") (class "Default")
      (node (ref "Q124") (pin "1") (pinfunction "C_1") (pintype "passive"))
      (node (ref "Q143") (pin "3") (pinfunction "E_3") (pintype "passive"))
    )
    (net (code "39") (name "Net-(Q125-C)") (class "Default")
      (node (ref "Q125") (pin "1") (pinfunction "C_1") (pintype "passive"))
      (node (ref "Q132") (pin "2") (pinfunction "B_2") (pintype "passive"))
      (node (ref "Q146") (pin "3") (pinfunction "E_3") (pintype "passive"))
    )
    (net (code "40") (name "Net-(Q126-C)") (class "Default")
      (node (ref "Q126") (pin "1") (pinfunction "C_1") (pintype "passive"))
      (node (ref "Q203") (pin "2") (pinfunction "B_2") (pintype "passive"))
      (node (ref "Q227") (pin "1") (pinfunction "C_1") (pintype "passive"))
    )
    (net (code "41") (name "Net-(Q127-C)") (class "Default")
      (node (ref "Q127") (pin "2") (pinfunction "C_2") (pintype "passive"))
      (node (ref "Q155") (pin "1") (pinfunction "E_1") (pintype "passive"))
      (node (ref "R1") (pin "1") (pinfunction "1_1") (pintype "passive"))
    )
    (net (code "42") (name "Net-(Q128-C)") (class "Default")
      (node (ref "Q128") (pin "2") (pinfunction "C_2") (pintype "passive"))
      (node (ref "Q129") (pin "2") (pinfunction "C_2") (pintype "passive"))
      (node (ref "Q135") (pin "3") (pinfunction "B_3") (pintype "passive"))
      (node (ref "Q156") (pin "1") (pinfunction "E_1") (pintype "passive"))
      (node (ref "Q157") (pin "1") (pinfunction "E_1") (pintype "passive"))
    )
    (net (code "43") (name "Net-(Q130-B)") (class "Default")
      (node (ref "Q130") (pin "3") (pinfunction "B_3") (pintype "passive"))
      (node (ref "Q131") (pin "3") (pinfunction "B_3") (pintype "passive"))
      (node (ref "Q138") (pin "1") (pinfunction "E_1") (pintype "passive"))
    )
    (net (code "44") (name "Net-(Q130-C)") (class "Default")
      (node (ref "Q130") (pin "2") (pinfunction "C_2") (pintype "passive"))
      (node (ref "Q131") (pin "2") (pinfunction "C_2") (pintype "passive"))
      (node (ref "Q138") (pin "3") (pinfunction "B_3") (pintype "passive"))
      (node (ref "Q148") (pin "1") (pinfunction "E_1") (pintype "passive"))
      (node (ref "Q149") (pin "1") (pinfunction "E_1") (pintype "passive"))
    )
    (net (code "45") (name "Net-(Q133-B)") (class "Default")
      (node (ref "Q133") (pin "3") (pinfunction "B_3") (pintype "passive"))
      (node (ref "Q134") (pin "3") (pinfunction "B_3") (pintype "passive"))
      (node (ref "Q139") (pin "1") (pinfunction "E_1") (pintype "passive"))
    )
    (net (code "46") (name "Net-(Q133-C)") (class "Default")
      (node (ref "Q133") (pin "2") (pinfunction "C_2") (pintype "passive"))
      (node (ref "Q134") (pin "2") (pinfunction "C_2") (pintype "passive"))
      (node (ref "Q139") (pin "3") (pinfunction "B_3") (pintype "passive"))
      (node (ref "Q153") (pin "1") (pinfunction "E_1") (pintype "passive"))
      (node (ref "Q154") (pin "1") (pinfunction "E_1") (pintype "passive"))
    )
    (net (code "47") (name "Net-(Q143-C)") (class "Default")
      (node (ref "Q143") (pin "1") (pinfunction "C_1") (pintype "passive"))
      (node (ref "Q170") (pin "1") (pinfunction "C_1") (pintype "passive"))
      (node (ref "Q170") (pin "2") (pinfunction "B_2") (pintype "passive"))
      (node (ref "Q171") (pin "2") (pinfunction "B_2") (pintype "passive"))
    )
    (net (code "48") (name "Net-(Q146-C)") (class "Default")
      (node (ref "Q146") (pin "1") (pinfunction "C_1") (pintype "passive"))
      (node (ref "Q162") (pin "2") (pinfunction "B_2") (pintype "passive"))
      (node (ref "Q171") (pin "1") (pinfunction "C_1") (pintype "passive"))
    )
    (net (code "49") (name "Net-(Q147-B)") (class "Default")
      (node (ref "Q147") (pin "3") (pinfunction "B_3") (pintype "passive"))
      (node (ref "Q155") (pin "3") (pinfunction "B_3") (pintype "passive"))
      (node (ref "Q156") (pin "3") (pinfunction "B_3") (pintype "passive"))
      (node (ref "Q157") (pin "3") (pinfunction "B_3") (pintype "passive"))
      (node (ref "Q164") (pin "1") (pinfunction "E_1") (pintype "passive"))
      (node (ref "R3") (pin "2") (pinfunction "2_2") (pintype "passive"))
      (node (ref "R4") (pin "2") (pinfunction "2_2") (pintype "passive"))
    )
    (net (code "50") (name "Net-(Q147-C)") (class "Default")
      (node (ref "C4") (pin "1") (pinfunction "1_1") (pintype "passive"))
      (node (ref "Q147") (pin "2") (pinfunction "C_2") (pintype "passive"))
      (node (ref "Q179") (pin "2") (pinfunction "C_2") (pintype "passive"))
      (node (ref "Q283") (pin "3") (pinfunction "B_3") (pintype "passive"))
      (node (ref "R13") (pin "2") (pinfunction "2_2") (pintype "passive"))
      (node (ref "R4") (pin "1") (pinfunction "1_1") (pintype "passive"))
      (node (ref "R6") (pin "2") (pinfunction "2_2") (pintype "passive"))
    )
    (net (code "51") (name "Net-(Q148-B)") (class "Default")
      (node (ref "Q148") (pin "3") (pinfunction "B_3") (pintype "passive"))
      (node (ref "Q149") (pin "3") (pinfunction "B_3") (pintype "passive"))
      (node (ref "Q165") (pin "1") (pinfunction "E_1") (pintype "passive"))
    )
    (net (code "52") (name "Net-(Q148-C)") (class "Default")
      (node (ref "Q148") (pin "2") (pinfunction "C_2") (pintype "passive"))
      (node (ref "Q149") (pin "2") (pinfunction "C_2") (pintype "passive"))
      (node (ref "Q165") (pin "3") (pinfunction "B_3") (pintype "passive"))
      (node (ref "Q166") (pin "3") (pinfunction "B_3") (pintype "passive"))
      (node (ref "Q176") (pin "2") (pinfunction "C_2") (pintype "passive"))
      (node (ref "Q177") (pin "2") (pinfunction "C_2") (pintype "passive"))
    )
    (net (code "53") (name "Net-(Q150-B)") (class "Default")
      (node (ref "P3") (pin "2") (pinfunction "2_2") (pintype "passive"))
      (node (ref "Q150") (pin "3") (pinfunction "B_3") (pintype "passive"))
      (node (ref "V10") (pin "1") (pinfunction "1_1") (pintype "passive"))
    )
    (net (code "54") (name "Net-(Q150-E)") (class "Default")
      (node (ref "C1") (pin "1") (pinfunction "1_1") (pintype "passive"))
      (node (ref "Q150") (pin "1") (pinfunction "E_1") (pintype "passive"))
      (node (ref "Q223") (pin "2") (pinfunction "C_2") (pintype "passive"))
    )
    (net (code "55") (name "Net-(Q151-E)") (class "Default")
      (node (ref "Q151") (pin "1") (pinfunction "E_1") (pintype "passive"))
      (node (ref "Q152") (pin "1") (pinfunction "E_1") (pintype "passive"))
      (node (ref "Q180") (pin "2") (pinfunction "C_2") (pintype "passive"))
      (node (ref "Q182") (pin "2") (pinfunction "C_2") (pintype "passive"))
      (node (ref "Q217") (pin "3") (pinfunction "B_3") (pintype "passive"))
    )
    (net (code "56") (name "Net-(Q153-B)") (class "Default")
      (node (ref "Q153") (pin "3") (pinfunction "B_3") (pintype "passive"))
      (node (ref "Q154") (pin "3") (pinfunction "B_3") (pintype "passive"))
      (node (ref "Q161") (pin "1") (pinfunction "E_1") (pintype "passive"))
    )
    (net (code "57") (name "Net-(Q153-C)") (class "Default")
      (node (ref "Q153") (pin "2") (pinfunction "C_2") (pintype "passive"))
      (node (ref "Q154") (pin "2") (pinfunction "C_2") (pintype "passive"))
      (node (ref "Q161") (pin "3") (pinfunction "B_3") (pintype "passive"))
      (node (ref "Q172") (pin "3") (pinfunction "B_3") (pintype "passive"))
      (node (ref "Q183") (pin "2") (pinfunction "C_2") (pintype "passive"))
      (node (ref "Q186") (pin "2") (pinfunction "C_2") (pintype "passive"))
    )
    (net (code "58") (name "Net-(Q155-C)") (class "Default")
      (node (ref "C5") (pin "1") (pinfunction "1_1") (pintype "passive"))
      (node (ref "Q155") (pin "2") (pinfunction "C_2") (pintype "passive"))
      (node (ref "Q189") (pin "2") (pinfunction "C_2") (pintype "passive"))
      (node (ref "Q288") (pin "3") (pinfunction "B_3") (pintype "passive"))
      (node (ref "R3") (pin "1") (pinfunction "1_1") (pintype "passive"))
      (node (ref "R5") (pin "2") (pinfunction "2_2") (pintype "passive"))
      (node (ref "R9") (pin "2") (pinfunction "2_2") (pintype "passive"))
    )
    (net (code "59") (name "Net-(Q156-C)") (class "Default")
      (node (ref "Q156") (pin "2") (pinfunction "C_2") (pintype "passive"))
      (node (ref "Q157") (pin "2") (pinfunction "C_2") (pintype "passive"))
      (node (ref "Q164") (pin "3") (pinfunction "B_3") (pintype "passive"))
      (node (ref "Q179") (pin "3") (pinfunction "B_3") (pintype "passive"))
      (node (ref "Q189") (pin "3") (pinfunction "B_3") (pintype "passive"))
      (node (ref "Q190") (pin "2") (pinfunction "C_2") (pintype "passive"))
      (node (ref "Q190") (pin "3") (pinfunction "B_3") (pintype "passive"))
      (node (ref "Q192") (pin "2") (pinfunction "C_2") (pintype "passive"))
      (node (ref "Q192") (pin "3") (pinfunction "B_3") (pintype "passive"))
      (node (ref "R5") (pin "1") (pinfunction "1_1") (pintype "passive"))
      (node (ref "R6") (pin "1") (pinfunction "1_1") (pintype "passive"))
    )
    (net (code "60") (name "Net-(Q158-E)") (class "Default")
      (node (ref "Q158") (pin "1") (pinfunction "E_1") (pintype "passive"))
      (node (ref "Q159") (pin "1") (pinfunction "E_1") (pintype "passive"))
      (node (ref "Q193") (pin "2") (pinfunction "C_2") (pintype "passive"))
      (node (ref "Q194") (pin "2") (pinfunction "C_2") (pintype "passive"))
      (node (ref "Q213") (pin "3") (pinfunction "B_3") (pintype "passive"))
    )
    (net (code "61") (name "Net-(Q160-B)") (class "Default")
      (node (ref "Q160") (pin "3") (pinfunction "B_3") (pintype "passive"))
      (node (ref "R15") (pin "1") (pinfunction "1_1") (pintype "passive"))
      (node (ref "R18") (pin "2") (pinfunction "2_2") (pintype "passive"))
    )
    (net (code "62") (name "Net-(Q160-E)") (class "Default")
      (node (ref "C2") (pin "1") (pinfunction "1_1") (pintype "passive"))
      (node (ref "Q160") (pin "1") (pinfunction "E_1") (pintype "passive"))
      (node (ref "Q221") (pin "2") (pinfunction "C_2") (pintype "passive"))
    )
    (net (code "63") (name "Net-(Q166-E)") (class "Default")
      (node (ref "Q166") (pin "1") (pinfunction "E_1") (pintype "passive"))
      (node (ref "Q176") (pin "3") (pinfunction "B_3") (pintype "passive"))
      (node (ref "Q177") (pin "3") (pinfunction "B_3") (pintype "passive"))
    )
    (net (code "64") (name "Net-(Q169-C)") (class "Default")
      (node (ref "Q169") (pin "1") (pinfunction "C_1") (pintype "passive"))
      (node (ref "Q246") (pin "2") (pinfunction "C_2") (pintype "passive"))
      (node (ref "Q246") (pin "3") (pinfunction "B_3") (pintype "passive"))
      (node (ref "Q247") (pin "3") (pinfunction "B_3") (pintype "passive"))
      (node (ref "Q248") (pin "3") (pinfunction "B_3") (pintype "passive"))
    )
    (net (code "65") (name "Net-(Q170-E)") (class "Default")
      (node (ref "Q170") (pin "3") (pinfunction "E_3") (pintype "passive"))
      (node (ref "Q199") (pin "1") (pinfunction "C_1") (pintype "passive"))
      (node (ref "Q199") (pin "2") (pinfunction "B_2") (pintype "passive"))
      (node (ref "Q200") (pin "2") (pinfunction "B_2") (pintype "passive"))
    )
    (net (code "66") (name "Net-(Q171-E)") (class "Default")
      (node (ref "Q171") (pin "3") (pinfunction "E_3") (pintype "passive"))
      (node (ref "Q200") (pin "1") (pinfunction "C_1") (pintype "passive"))
    )
    (net (code "67") (name "Net-(Q172-E)") (class "Default")
      (node (ref "Q172") (pin "1") (pinfunction "E_1") (pintype "passive"))
      (node (ref "Q183") (pin "3") (pinfunction "B_3") (pintype "passive"))
      (node (ref "Q186") (pin "3") (pinfunction "B_3") (pintype "passive"))
    )
    (net (code "68") (name "Net-(Q176-E)") (class "Default")
      (node (ref "C2") (pin "2") (pinfunction "2_2") (pintype "passive"))
      (node (ref "Q176") (pin "1") (pinfunction "E_1") (pintype "passive"))
      (node (ref "Q177") (pin "1") (pinfunction "E_1") (pintype "passive"))
      (node (ref "Q225") (pin "2") (pinfunction "C_2") (pintype "passive"))
      (node (ref "Q225") (pin "3") (pinfunction "B_3") (pintype "passive"))
      (node (ref "Q226") (pin "2") (pinfunction "C_2") (pintype "passive"))
      (node (ref "Q226") (pin "3") (pinfunction "B_3") (pintype "passive"))
      (node (ref "R17") (pin "1") (pinfunction "1_1") (pintype "passive"))
    )
    (net (code "69") (name "Net-(Q179-E)") (class "Default")
      (node (ref "Q179") (pin "1") (pinfunction "E_1") (pintype "passive"))
      (node (ref "Q224") (pin "2") (pinfunction "C_2") (pintype "passive"))
      (node (ref "R8") (pin "2") (pinfunction "2_2") (pintype "passive"))
    )
    (net (code "70") (name "Net-(Q180-B)") (class "Default")
      (node (ref "Q180") (pin "3") (pinfunction "B_3") (pintype "passive"))
      (node (ref "Q182") (pin "3") (pinfunction "B_3") (pintype "passive"))
      (node (ref "Q217") (pin "1") (pinfunction "E_1") (pintype "passive"))
    )
    (net (code "71") (name "Net-(Q180-E)") (class "Default")
      (node (ref "Q180") (pin "1") (pinfunction "E_1") (pintype "passive"))
      (node (ref "Q182") (pin "1") (pinfunction "E_1") (pintype "passive"))
      (node (ref "Q214") (pin "2") (pinfunction "C_2") (pintype "passive"))
      (node (ref "Q265") (pin "3") (pinfunction "B_3") (pintype "passive"))
    )
    (net (code "72") (name "Net-(Q183-E)") (class "Default")
      (node (ref "C1") (pin "2") (pinfunction "2_2") (pintype "passive"))
      (node (ref "Q183") (pin "1") (pinfunction "E_1") (pintype "passive"))
      (node (ref "Q186") (pin "1") (pinfunction "E_1") (pintype "passive"))
      (node (ref "Q228") (pin "2") (pinfunction "C_2") (pintype "passive"))
      (node (ref "Q228") (pin "3") (pinfunction "B_3") (pintype "passive"))
      (node (ref "Q229") (pin "2") (pinfunction "C_2") (pintype "passive"))
      (node (ref "Q229") (pin "3") (pinfunction "B_3") (pintype "passive"))
      (node (ref "R14") (pin "2") (pinfunction "2_2") (pintype "passive"))
    )
    (net (code "73") (name "Net-(Q189-E)") (class "Default")
      (node (ref "Q189") (pin "1") (pinfunction "E_1") (pintype "passive"))
      (node (ref "Q231") (pin "2") (pinfunction "C_2") (pintype "passive"))
      (node (ref "R7") (pin "2") (pinfunction "2_2") (pintype "passive"))
    )
    (net (code "74") (name "Net-(Q190-E)") (class "Default")
      (node (ref "Q190") (pin "1") (pinfunction "E_1") (pintype "passive"))
      (node (ref "Q192") (pin "1") (pinfunction "E_1") (pintype "passive"))
      (node (ref "Q233") (pin "2") (pinfunction "C_2") (pintype "passive"))
      (node (ref "Q233") (pin "3") (pinfunction "B_3") (pintype "passive"))
      (node (ref "Q234") (pin "2") (pinfunction "C_2") (pintype "passive"))
      (node (ref "Q234") (pin "3") (pinfunction "B_3") (pintype "passive"))
    )
    (net (code "75") (name "Net-(Q193-B)") (class "Default")
      (node (ref "Q193") (pin "3") (pinfunction "B_3") (pintype "passive"))
      (node (ref "Q194") (pin "3") (pinfunction "B_3") (pintype "passive"))
      (node (ref "Q213") (pin "1") (pinfunction "E_1") (pintype "passive"))
    )
    (net (code "76") (name "Net-(Q193-E)") (class "Default")
      (node (ref "Q193") (pin "1") (pinfunction "E_1") (pintype "passive"))
      (node (ref "Q194") (pin "1") (pinfunction "E_1") (pintype "passive"))
      (node (ref "Q215") (pin "2") (pinfunction "C_2") (pintype "passive"))
      (node (ref "Q264") (pin "3") (pinfunction "B_3") (pintype "passive"))
    )
    (net (code "77") (name "Net-(Q195-E)") (class "Default")
      (node (ref "Q195") (pin "1") (pinfunction "E_1") (pintype "passive"))
      (node (ref "Q197") (pin "1") (pinfunction "E_1") (pintype "passive"))
      (node (ref "Q219") (pin "2") (pinfunction "C_2") (pintype "passive"))
      (node (ref "Q220") (pin "2") (pinfunction "C_2") (pintype "passive"))
      (node (ref "Q261") (pin "3") (pinfunction "B_3") (pintype "passive"))
    )
    (net (code "78") (name "Net-(Q199-E)") (class "Default")
      (node (ref "Q199") (pin "3") (pinfunction "E_3") (pintype "passive"))
      (node (ref "Q251") (pin "3") (pinfunction "E_3") (pintype "passive"))
    )
    (net (code "79") (name "Net-(Q200-E)") (class "Default")
      (node (ref "Q200") (pin "3") (pinfunction "E_3") (pintype "passive"))
      (node (ref "R10") (pin "2") (pinfunction "2_2") (pintype "passive"))
    )
    (net (code "80") (name "Net-(Q212-C)") (class "Default")
      (node (ref "Q212") (pin "1") (pinfunction "C_1") (pintype "passive"))
      (node (ref "Q238") (pin "2") (pinfunction "C_2") (pintype "passive"))
      (node (ref "Q238") (pin "3") (pinfunction "B_3") (pintype "passive"))
      (node (ref "Q240") (pin "3") (pinfunction "B_3") (pintype "passive"))
      (node (ref "Q245") (pin "3") (pinfunction "B_3") (pintype "passive"))
    )
    (net (code "81") (name "Net-(Q214-B)") (class "Default")
      (node (ref "Q214") (pin "3") (pinfunction "B_3") (pintype "passive"))
      (node (ref "Q265") (pin "1") (pinfunction "E_1") (pintype "passive"))
    )
    (net (code "82") (name "Net-(Q215-B)") (class "Default")
      (node (ref "Q215") (pin "3") (pinfunction "B_3") (pintype "passive"))
      (node (ref "Q264") (pin "1") (pinfunction "E_1") (pintype "passive"))
    )
    (net (code "83") (name "Net-(Q219-B)") (class "Default")
      (node (ref "Q219") (pin "3") (pinfunction "B_3") (pintype "passive"))
      (node (ref "Q220") (pin "3") (pinfunction "B_3") (pintype "passive"))
      (node (ref "Q221") (pin "3") (pinfunction "B_3") (pintype "passive"))
      (node (ref "Q223") (pin "3") (pinfunction "B_3") (pintype "passive"))
      (node (ref "Q261") (pin "1") (pinfunction "E_1") (pintype "passive"))
    )
    (net (code "84") (name "Net-(Q219-E)") (class "Default")
      (node (ref "Q219") (pin "1") (pinfunction "E_1") (pintype "passive"))
      (node (ref "Q220") (pin "1") (pinfunction "E_1") (pintype "passive"))
      (node (ref "Q242") (pin "2") (pinfunction "C_2") (pintype "passive"))
      (node (ref "Q262") (pin "3") (pinfunction "B_3") (pintype "passive"))
    )
    (net (code "85") (name "Net-(Q221-E)") (class "Default")
      (node (ref "Q221") (pin "1") (pinfunction "E_1") (pintype "passive"))
      (node (ref "Q223") (pin "1") (pinfunction "E_1") (pintype "passive"))
      (node (ref "Q243") (pin "2") (pinfunction "C_2") (pintype "passive"))
    )
    (net (code "86") (name "Net-(Q224-B)") (class "Default")
      (node (ref "Q224") (pin "3") (pinfunction "B_3") (pintype "passive"))
      (node (ref "R13") (pin "1") (pinfunction "1_1") (pintype "passive"))
      (node (ref "R17") (pin "2") (pinfunction "2_2") (pintype "passive"))
      (node (ref "R8") (pin "1") (pinfunction "1_1") (pintype "passive"))
    )
    (net (code "87") (name "Net-(Q224-E)") (class "Default")
      (node (ref "Q224") (pin "1") (pinfunction "E_1") (pintype "passive"))
      (node (ref "Q231") (pin "1") (pinfunction "E_1") (pintype "passive"))
      (node (ref "Q247") (pin "2") (pinfunction "C_2") (pintype "passive"))
    )
    (net (code "88") (name "Net-(Q225-E)") (class "Default")
      (node (ref "Q225") (pin "1") (pinfunction "E_1") (pintype "passive"))
      (node (ref "Q226") (pin "1") (pinfunction "E_1") (pintype "passive"))
      (node (ref "Q240") (pin "2") (pinfunction "C_2") (pintype "passive"))
    )
    (net (code "89") (name "Net-(Q228-E)") (class "Default")
      (node (ref "Q228") (pin "1") (pinfunction "E_1") (pintype "passive"))
      (node (ref "Q229") (pin "1") (pinfunction "E_1") (pintype "passive"))
      (node (ref "Q245") (pin "2") (pinfunction "C_2") (pintype "passive"))
    )
    (net (code "90") (name "Net-(Q231-B)") (class "Default")
      (node (ref "Q231") (pin "3") (pinfunction "B_3") (pintype "passive"))
      (node (ref "R14") (pin "1") (pinfunction "1_1") (pintype "passive"))
      (node (ref "R7") (pin "1") (pinfunction "1_1") (pintype "passive"))
      (node (ref "R9") (pin "1") (pinfunction "1_1") (pintype "passive"))
    )
    (net (code "91") (name "Net-(Q233-E)") (class "Default")
      (node (ref "Q233") (pin "1") (pinfunction "E_1") (pintype "passive"))
      (node (ref "Q234") (pin "1") (pinfunction "E_1") (pintype "passive"))
      (node (ref "Q248") (pin "2") (pinfunction "C_2") (pintype "passive"))
    )
    (net (code "92") (name "Net-(Q242-B)") (class "Default")
      (node (ref "Q242") (pin "3") (pinfunction "B_3") (pintype "passive"))
      (node (ref "Q243") (pin "3") (pinfunction "B_3") (pintype "passive"))
      (node (ref "Q262") (pin "1") (pinfunction "E_1") (pintype "passive"))
    )
    (net (code "93") (name "Net-(Q252-E)") (class "Default")
      (node (ref "Q252") (pin "3") (pinfunction "E_3") (pintype "passive"))
      (node (ref "Q254") (pin "3") (pinfunction "E_3") (pintype "passive"))
      (node (ref "Q255") (pin "3") (pinfunction "E_3") (pintype "passive"))
      (node (ref "Q257") (pin "3") (pinfunction "E_3") (pintype "passive"))
      (node (ref "Q258") (pin "3") (pinfunction "E_3") (pintype "passive"))
      (node (ref "R10") (pin "1") (pinfunction "1_1") (pintype "passive"))
    )
    (net (code "94") (name "Net-(Q274-B)") (class "Default")
      (node (ref "Q274") (pin "3") (pinfunction "B_3") (pintype "passive"))
      (node (ref "Q275") (pin "2") (pinfunction "C_2") (pintype "passive"))
      (node (ref "Q275") (pin "3") (pinfunction "B_3") (pintype "passive"))
      (node (ref "Q283") (pin "1") (pinfunction "E_1") (pintype "passive"))
    )
    (net (code "95") (name "Net-(Q274-C)") (class "Default")
      (node (ref "Q274") (pin "2") (pinfunction "C_2") (pintype "passive"))
      (node (ref "Q288") (pin "1") (pinfunction "E_1") (pintype "passive"))
      (node (ref "R11") (pin "1") (pinfunction "1_1") (pintype "passive"))
    )
    (net (code "96") (name "Net-(Q279-C)") (class "Default")
      (node (ref "Q279") (pin "1") (pinfunction "C_1") (pintype "passive"))
      (node (ref "Q289") (pin "2") (pinfunction "C_2") (pintype "passive"))
      (node (ref "Q289") (pin "3") (pinfunction "B_3") (pintype "passive"))
      (node (ref "Q292") (pin "3") (pinfunction "B_3") (pintype "passive"))
    )
    (net (code "97") (name "Net-(Q283-C)") (class "Default")
      (node (ref "Q283") (pin "2") (pinfunction "C_2") (pintype "passive"))
      (node (ref "Q288") (pin "2") (pinfunction "C_2") (pintype "passive"))
      (node (ref "Q292") (pin "2") (pinfunction "C_2") (pintype "passive"))
    )
    (net (code "98") (name "Net-(R15-Pad2)") (class "Default")
      (node (ref "R15") (pin "2") (pinfunction "2_2") (pintype "passive"))
      (node (ref "R16") (pin "1") (pinfunction "1_1") (pintype "passive"))
    )
    (net (code "99") (name "Net-(R16-Pad2)") (class "Default")
      (node (ref "R16") (pin "2") (pinfunction "2_2") (pintype "passive"))
      (node (ref "R26") (pin "1") (pinfunction "1_1") (pintype "passive"))
    )
    (net (code "100") (name "unconnected-(J1-RING_SWITCH-Pad4)") (class "Default")
      (node (ref "J1") (pin "4") (pinfunction "RING_SWITCH_4") (pintype "passive"))
    )
    (net (code "101") (name "unconnected-(J1-TIP_SWITCH-Pad5)") (class "Default")
      (node (ref "J1") (pin "5") (pinfunction "TIP_SWITCH_5") (pintype "passive"))
    )
  )
)
